# CM5_Adapter.net
KiCad netlist of a schematic drawn in Altium Designer
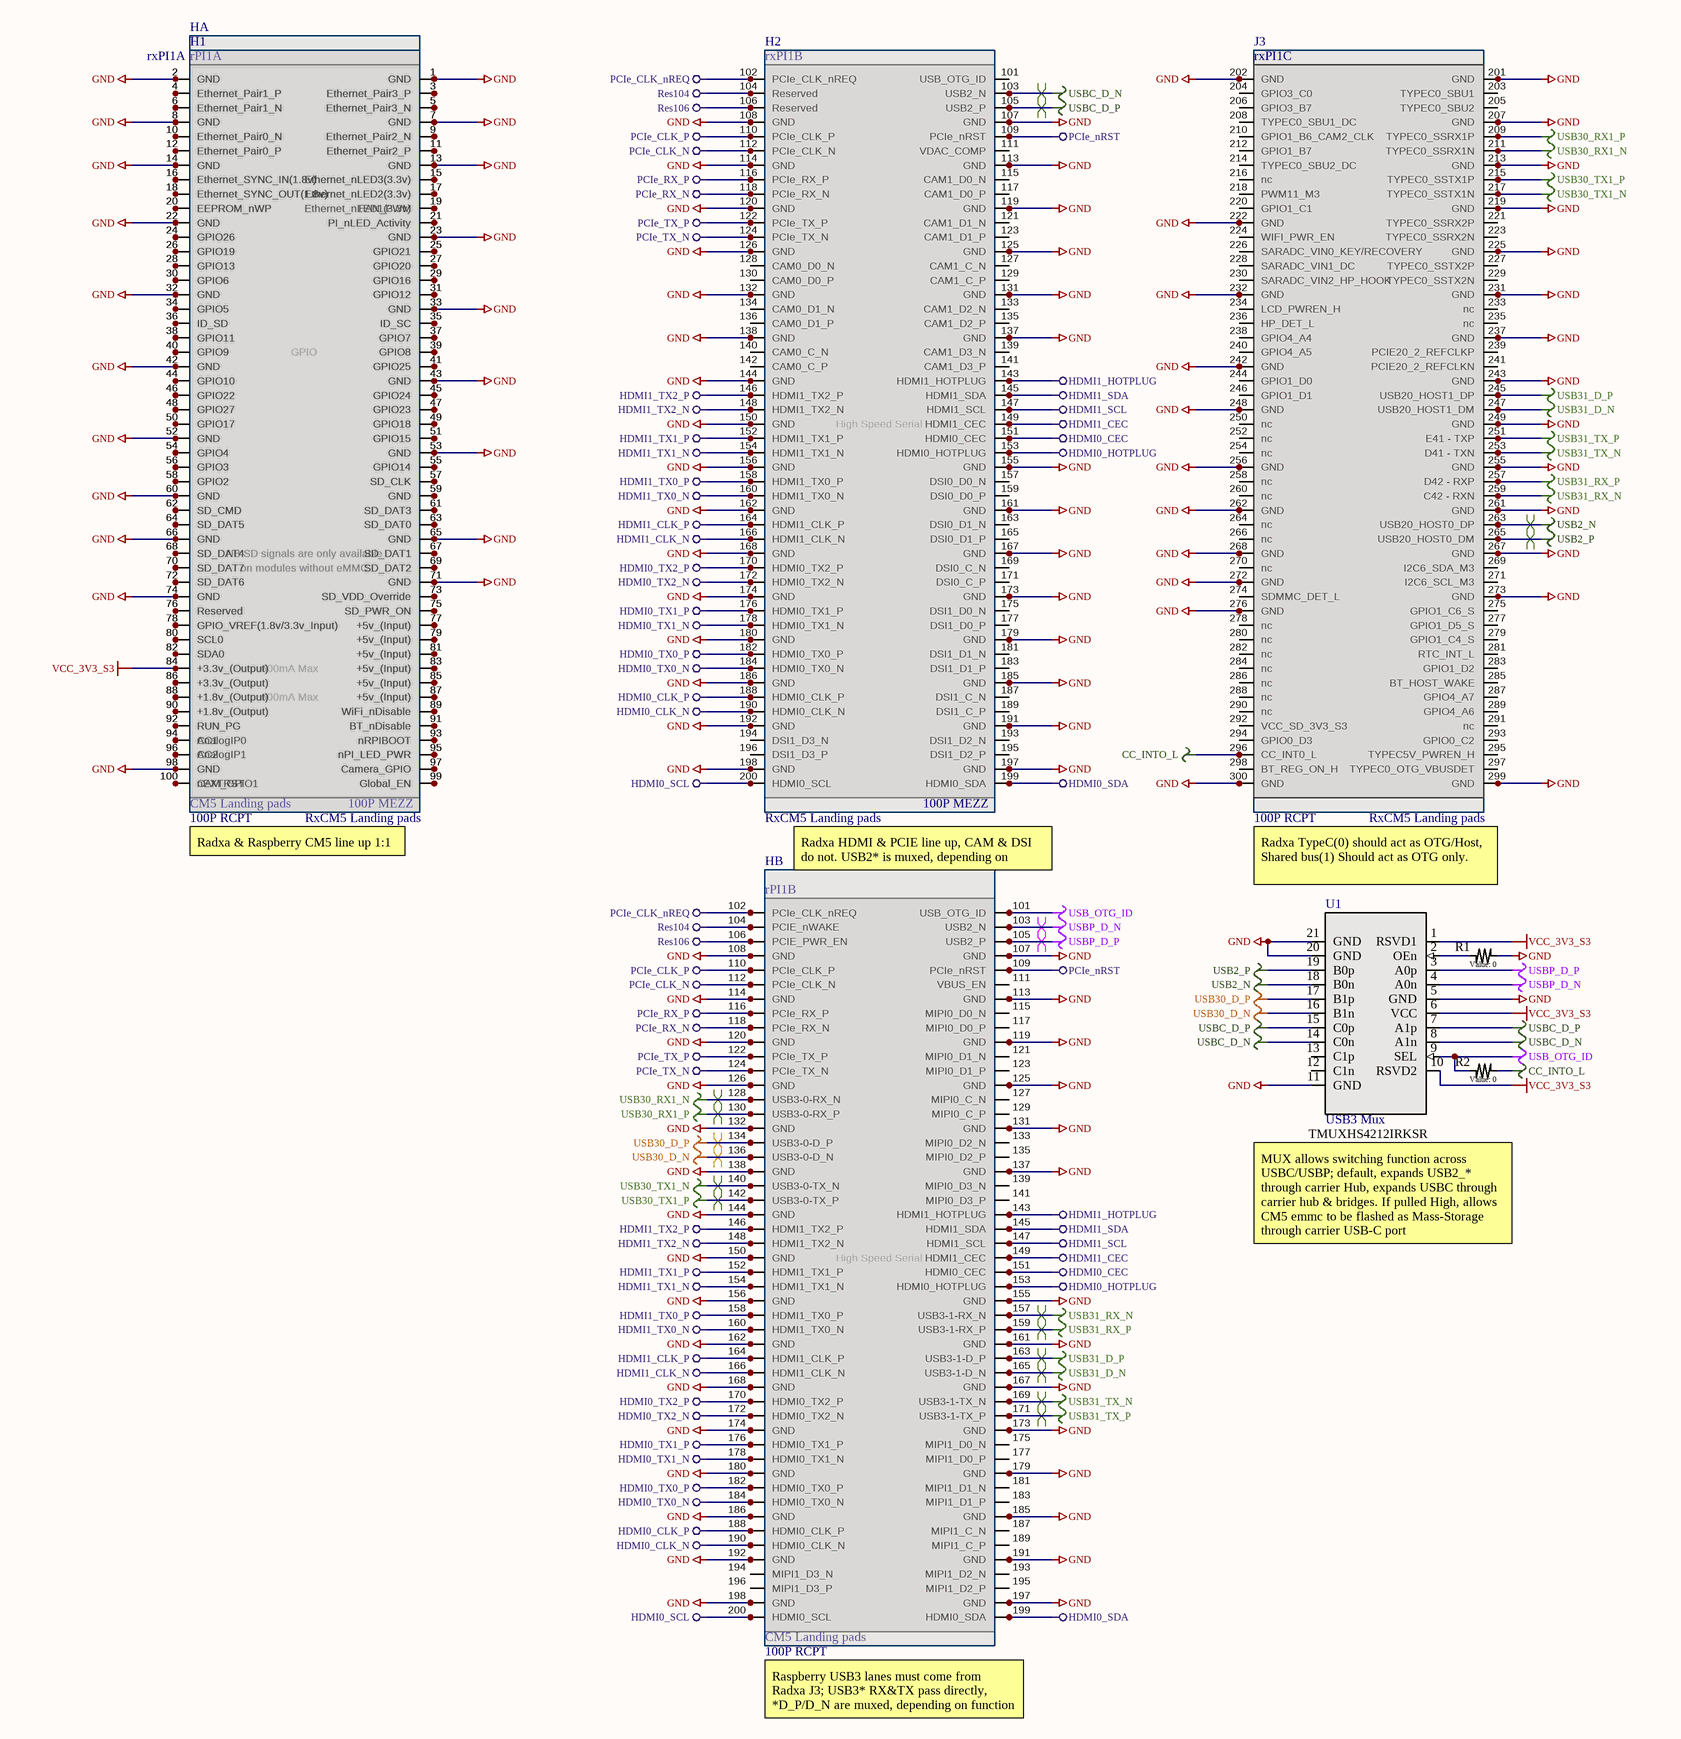
[diagram p0: CM5 Adapter.SchDoc]

(export (version "E")
  (design (tool "Eeschema 10.0.6"))
  (components
    (comp (ref "H1")
      (value "100P RCPT")
      (footprint "DF40C-100DS-0.4V(51)")
      (description "100 Position Connector Receptacle, Center Strip Contacts Surface Mount Gold")
      (fields (field (name "MF") "Hirose") (field (name "MP") "DF40C-100DS-0.4V(51)"))
      (libsource (lib "") (part "DF40-100DS RCPT_1_1"))
    )
    (comp (ref "H2")
      (value "100P MEZZ")
      (footprint "DF40C-100DS-0.4V(51)")
      (description "100 Position Connector Receptacle, Center Strip Contacts Surface Mount Gold")
      (fields (field (name "MF") "Hirose") (field (name "MP") "DF40C-100DS-0.4V(51)"))
      (libsource (lib "") (part "DF40-100DS RCPT_1_1"))
    )
    (comp (ref "HA")
      (value "100P MEZZ")
      (footprint "DF40C-100DP-0.4V(51)")
      (description "100 Position Connector Receptacle, Center Strip Contacts Surface Mount Gold")
      (fields (field (name "MF") "Hirose") (field (name "MP") "DF40C-100DS-0.4V(51)"))
      (libsource (lib "SOC_Carrier") (part "DF40-XX-100DS RCPT"))
    )
    (comp (ref "HB")
      (value "100P RCPT")
      (footprint "DF40C-100DP-0.4V(51)")
      (description "100 Position Connector Receptacle, Center Strip Contacts Surface Mount Gold")
      (fields (field (name "MF") "Hirose") (field (name "MP") "DF40C-100DS-0.4V(51)"))
      (libsource (lib "SOC_Carrier") (part "DF40-XX-100DS RCPT"))
    )
    (comp (ref "J3")
      (value "100P RCPT")
      (footprint "DF40C-100DS-0.4V(51)")
      (description "100 Position Connector Receptacle, Center Strip Contacts Surface Mount Gold")
      (fields (field (name "MF") "Hirose") (field (name "MP") "DF40C-100DS-0.4V(51)"))
      (libsource (lib "Connectors") (part "DF40-100DS RCPT_1"))
    )
    (comp (ref "R1")
      (value "0")
      (footprint "0603")
      (fields
        (field (name "TOLERANCE") "1%")
        (field (name "POWER") "1/10W")
        (field (name "Comment") "Generic Resistor")
      )
      (libsource (lib "Resistors") (part "Generic Resistor"))
    )
    (comp (ref "R2")
      (value "0")
      (footprint "0603")
      (fields
        (field (name "TOLERANCE") "1%")
        (field (name "POWER") "1/10W")
        (field (name "Comment") "Generic Resistor")
      )
      (libsource (lib "Resistors") (part "Generic Resistor"))
    )
    (comp (ref "rPI1")
      (value "CM5 Landing pads")
      (footprint "rP-200P-CM-REP (top)")
      (libsource (lib "SOC_Carrier") (part "RP-CM5-Rep"))
    )
    (comp (ref "rxPI1")
      (value "RxCM5 Landing pads")
      (footprint "RX-300P-CM-FTPD")
      (libsource (lib "SOC_Carrier") (part "RX-CM5"))
    )
    (comp (ref "U1")
      (value "USB3 Mux")
      (footprint "QFN50P450X250X100-21N")
      (description "2-channel 16-Gbps 2:1/1:2 differential mux/demux")
      (fields
        (field (name "MANUFACTURER_PART_NUMBER") "TMUXHS4212IRKSR")
        (field (name "COPYRIGHT") "Copyright (C) 2023 Ultra Librarian. All rights reserved.")
      )
      (libsource (lib "Misc ICs") (part "TMUXHS4212IRKSR"))
    )
  )
  (nets
    (net (code "1") (name "CC_INTO_L") (class "Default")
      (node (ref "J3") (pin "95") (pinfunction "95_95") (pintype "passive"))
      (node (ref "R2") (pin "2") (pinfunction "2_2") (pintype "passive"))
      (node (ref "rxPI1") (pin "296") (pinfunction "CC_INT0_L_296") (pintype "passive"))
    )
    (net (code "2") (name "GND") (class "Default")
      (node (ref "H1") (pin "1") (pinfunction "1_1") (pintype "passive"))
      (node (ref "H1") (pin "13") (pinfunction "13_13") (pintype "passive"))
      (node (ref "H1") (pin "14") (pinfunction "14_14") (pintype "passive"))
      (node (ref "H1") (pin "2") (pinfunction "2_2") (pintype "passive"))
      (node (ref "H1") (pin "22") (pinfunction "22_22") (pintype "passive"))
      (node (ref "H1") (pin "23") (pinfunction "23_23") (pintype "passive"))
      (node (ref "H1") (pin "32") (pinfunction "32_32") (pintype "passive"))
      (node (ref "H1") (pin "33") (pinfunction "33_33") (pintype "passive"))
      (node (ref "H1") (pin "42") (pinfunction "42_42") (pintype "passive"))
      (node (ref "H1") (pin "43") (pinfunction "43_43") (pintype "passive"))
      (node (ref "H1") (pin "52") (pinfunction "52_52") (pintype "passive"))
      (node (ref "H1") (pin "53") (pinfunction "53_53") (pintype "passive"))
      (node (ref "H1") (pin "60") (pinfunction "60_60") (pintype "passive"))
      (node (ref "H1") (pin "65") (pinfunction "65_65") (pintype "passive"))
      (node (ref "H1") (pin "66") (pinfunction "66_66") (pintype "passive"))
      (node (ref "H1") (pin "7") (pinfunction "7_7") (pintype "passive"))
      (node (ref "H1") (pin "71") (pinfunction "71_71") (pintype "passive"))
      (node (ref "H1") (pin "74") (pinfunction "74_74") (pintype "passive"))
      (node (ref "H1") (pin "8") (pinfunction "8_8") (pintype "passive"))
      (node (ref "H1") (pin "98") (pinfunction "98_98") (pintype "passive"))
      (node (ref "H2") (pin "13") (pinfunction "13_13") (pintype "passive"))
      (node (ref "H2") (pin "14") (pinfunction "14_14") (pintype "passive"))
      (node (ref "H2") (pin "19") (pinfunction "19_19") (pintype "passive"))
      (node (ref "H2") (pin "20") (pinfunction "20_20") (pintype "passive"))
      (node (ref "H2") (pin "25") (pinfunction "25_25") (pintype "passive"))
      (node (ref "H2") (pin "26") (pinfunction "26_26") (pintype "passive"))
      (node (ref "H2") (pin "31") (pinfunction "31_31") (pintype "passive"))
      (node (ref "H2") (pin "32") (pinfunction "32_32") (pintype "passive"))
      (node (ref "H2") (pin "37") (pinfunction "37_37") (pintype "passive"))
      (node (ref "H2") (pin "38") (pinfunction "38_38") (pintype "passive"))
      (node (ref "H2") (pin "44") (pinfunction "44_44") (pintype "passive"))
      (node (ref "H2") (pin "50") (pinfunction "50_50") (pintype "passive"))
      (node (ref "H2") (pin "55") (pinfunction "55_55") (pintype "passive"))
      (node (ref "H2") (pin "56") (pinfunction "56_56") (pintype "passive"))
      (node (ref "H2") (pin "61") (pinfunction "61_61") (pintype "passive"))
      (node (ref "H2") (pin "62") (pinfunction "62_62") (pintype "passive"))
      (node (ref "H2") (pin "67") (pinfunction "67_67") (pintype "passive"))
      (node (ref "H2") (pin "68") (pinfunction "68_68") (pintype "passive"))
      (node (ref "H2") (pin "7") (pinfunction "7_7") (pintype "passive"))
      (node (ref "H2") (pin "73") (pinfunction "73_73") (pintype "passive"))
      (node (ref "H2") (pin "74") (pinfunction "74_74") (pintype "passive"))
      (node (ref "H2") (pin "79") (pinfunction "79_79") (pintype "passive"))
      (node (ref "H2") (pin "8") (pinfunction "8_8") (pintype "passive"))
      (node (ref "H2") (pin "80") (pinfunction "80_80") (pintype "passive"))
      (node (ref "H2") (pin "85") (pinfunction "85_85") (pintype "passive"))
      (node (ref "H2") (pin "86") (pinfunction "86_86") (pintype "passive"))
      (node (ref "H2") (pin "91") (pinfunction "91_91") (pintype "passive"))
      (node (ref "H2") (pin "92") (pinfunction "92_92") (pintype "passive"))
      (node (ref "H2") (pin "97") (pinfunction "97_97") (pintype "passive"))
      (node (ref "H2") (pin "98") (pinfunction "98_98") (pintype "passive"))
      (node (ref "HA") (pin "1") (pinfunction "1_1") (pintype "passive"))
      (node (ref "HA") (pin "13") (pinfunction "13_13") (pintype "passive"))
      (node (ref "HA") (pin "14") (pinfunction "14_14") (pintype "passive"))
      (node (ref "HA") (pin "2") (pinfunction "2_2") (pintype "passive"))
      (node (ref "HA") (pin "21") (pinfunction "21_21") (pintype "passive"))
      (node (ref "HA") (pin "24") (pinfunction "24_24") (pintype "passive"))
      (node (ref "HA") (pin "31") (pinfunction "31_31") (pintype "passive"))
      (node (ref "HA") (pin "34") (pinfunction "34_34") (pintype "passive"))
      (node (ref "HA") (pin "41") (pinfunction "41_41") (pintype "passive"))
      (node (ref "HA") (pin "44") (pinfunction "44_44") (pintype "passive"))
      (node (ref "HA") (pin "51") (pinfunction "51_51") (pintype "passive"))
      (node (ref "HA") (pin "54") (pinfunction "54_54") (pintype "passive"))
      (node (ref "HA") (pin "59") (pinfunction "59_59") (pintype "passive"))
      (node (ref "HA") (pin "65") (pinfunction "65_65") (pintype "passive"))
      (node (ref "HA") (pin "66") (pinfunction "66_66") (pintype "passive"))
      (node (ref "HA") (pin "7") (pinfunction "7_7") (pintype "passive"))
      (node (ref "HA") (pin "72") (pinfunction "72_72") (pintype "passive"))
      (node (ref "HA") (pin "73") (pinfunction "73_73") (pintype "passive"))
      (node (ref "HA") (pin "8") (pinfunction "8_8") (pintype "passive"))
      (node (ref "HA") (pin "97") (pinfunction "97_97") (pintype "passive"))
      (node (ref "HB") (pin "13") (pinfunction "13_13") (pintype "passive"))
      (node (ref "HB") (pin "14") (pinfunction "14_14") (pintype "passive"))
      (node (ref "HB") (pin "19") (pinfunction "19_19") (pintype "passive"))
      (node (ref "HB") (pin "20") (pinfunction "20_20") (pintype "passive"))
      (node (ref "HB") (pin "25") (pinfunction "25_25") (pintype "passive"))
      (node (ref "HB") (pin "26") (pinfunction "26_26") (pintype "passive"))
      (node (ref "HB") (pin "31") (pinfunction "31_31") (pintype "passive"))
      (node (ref "HB") (pin "32") (pinfunction "32_32") (pintype "passive"))
      (node (ref "HB") (pin "37") (pinfunction "37_37") (pintype "passive"))
      (node (ref "HB") (pin "38") (pinfunction "38_38") (pintype "passive"))
      (node (ref "HB") (pin "43") (pinfunction "43_43") (pintype "passive"))
      (node (ref "HB") (pin "49") (pinfunction "49_49") (pintype "passive"))
      (node (ref "HB") (pin "55") (pinfunction "55_55") (pintype "passive"))
      (node (ref "HB") (pin "56") (pinfunction "56_56") (pintype "passive"))
      (node (ref "HB") (pin "61") (pinfunction "61_61") (pintype "passive"))
      (node (ref "HB") (pin "62") (pinfunction "62_62") (pintype "passive"))
      (node (ref "HB") (pin "67") (pinfunction "67_67") (pintype "passive"))
      (node (ref "HB") (pin "68") (pinfunction "68_68") (pintype "passive"))
      (node (ref "HB") (pin "7") (pinfunction "7_7") (pintype "passive"))
      (node (ref "HB") (pin "73") (pinfunction "73_73") (pintype "passive"))
      (node (ref "HB") (pin "74") (pinfunction "74_74") (pintype "passive"))
      (node (ref "HB") (pin "79") (pinfunction "79_79") (pintype "passive"))
      (node (ref "HB") (pin "8") (pinfunction "8_8") (pintype "passive"))
      (node (ref "HB") (pin "80") (pinfunction "80_80") (pintype "passive"))
      (node (ref "HB") (pin "85") (pinfunction "85_85") (pintype "passive"))
      (node (ref "HB") (pin "86") (pinfunction "86_86") (pintype "passive"))
      (node (ref "HB") (pin "91") (pinfunction "91_91") (pintype "passive"))
      (node (ref "HB") (pin "92") (pinfunction "92_92") (pintype "passive"))
      (node (ref "HB") (pin "97") (pinfunction "97_97") (pintype "passive"))
      (node (ref "HB") (pin "98") (pinfunction "98_98") (pintype "passive"))
      (node (ref "J3") (pin "1") (pinfunction "1_1") (pintype "passive"))
      (node (ref "J3") (pin "100") (pinfunction "100_100") (pintype "passive"))
      (node (ref "J3") (pin "14") (pinfunction "14_14") (pintype "passive"))
      (node (ref "J3") (pin "2") (pinfunction "2_2") (pintype "passive"))
      (node (ref "J3") (pin "20") (pinfunction "20_20") (pintype "passive"))
      (node (ref "J3") (pin "21") (pinfunction "21_21") (pintype "passive"))
      (node (ref "J3") (pin "26") (pinfunction "26_26") (pintype "passive"))
      (node (ref "J3") (pin "31") (pinfunction "31_31") (pintype "passive"))
      (node (ref "J3") (pin "32") (pinfunction "32_32") (pintype "passive"))
      (node (ref "J3") (pin "38") (pinfunction "38_38") (pintype "passive"))
      (node (ref "J3") (pin "41") (pinfunction "41_41") (pintype "passive"))
      (node (ref "J3") (pin "44") (pinfunction "44_44") (pintype "passive"))
      (node (ref "J3") (pin "47") (pinfunction "47_47") (pintype "passive"))
      (node (ref "J3") (pin "50") (pinfunction "50_50") (pintype "passive"))
      (node (ref "J3") (pin "55") (pinfunction "55_55") (pintype "passive"))
      (node (ref "J3") (pin "56") (pinfunction "56_56") (pintype "passive"))
      (node (ref "J3") (pin "61") (pinfunction "61_61") (pintype "passive"))
      (node (ref "J3") (pin "62") (pinfunction "62_62") (pintype "passive"))
      (node (ref "J3") (pin "67") (pinfunction "67_67") (pintype "passive"))
      (node (ref "J3") (pin "68") (pinfunction "68_68") (pintype "passive"))
      (node (ref "J3") (pin "71") (pinfunction "71_71") (pintype "passive"))
      (node (ref "J3") (pin "74") (pinfunction "74_74") (pintype "passive"))
      (node (ref "J3") (pin "75") (pinfunction "75_75") (pintype "passive"))
      (node (ref "J3") (pin "8") (pinfunction "8_8") (pintype "passive"))
      (node (ref "J3") (pin "99") (pinfunction "99_99") (pintype "passive"))
      (node (ref "R1") (pin "2") (pinfunction "2_2") (pintype "passive"))
      (node (ref "U1") (pin "11") (pinfunction "GND_11") (pintype "power_in"))
      (node (ref "U1") (pin "20") (pinfunction "GND_20") (pintype "power_in"))
      (node (ref "U1") (pin "21") (pinfunction "GND_21") (pintype "power_in"))
      (node (ref "U1") (pin "5") (pinfunction "GND_5") (pintype "power_in"))
      (node (ref "rPI1") (pin "1") (pinfunction "GND_1") (pintype "passive"))
      (node (ref "rPI1") (pin "107") (pinfunction "GND_107") (pintype "passive"))
      (node (ref "rPI1") (pin "108") (pinfunction "GND_108") (pintype "passive"))
      (node (ref "rPI1") (pin "113") (pinfunction "GND_113") (pintype "passive"))
      (node (ref "rPI1") (pin "114") (pinfunction "GND_114") (pintype "passive"))
      (node (ref "rPI1") (pin "119") (pinfunction "GND_119") (pintype "passive"))
      (node (ref "rPI1") (pin "120") (pinfunction "GND_120") (pintype "passive"))
      (node (ref "rPI1") (pin "125") (pinfunction "GND_125") (pintype "passive"))
      (node (ref "rPI1") (pin "126") (pinfunction "GND_126") (pintype "passive"))
      (node (ref "rPI1") (pin "13") (pinfunction "GND_13") (pintype "passive"))
      (node (ref "rPI1") (pin "131") (pinfunction "GND_131") (pintype "passive"))
      (node (ref "rPI1") (pin "132") (pinfunction "GND_132") (pintype "passive"))
      (node (ref "rPI1") (pin "137") (pinfunction "GND_137") (pintype "passive"))
      (node (ref "rPI1") (pin "138") (pinfunction "GND_138") (pintype "passive"))
      (node (ref "rPI1") (pin "14") (pinfunction "GND_14") (pintype "passive"))
      (node (ref "rPI1") (pin "144") (pinfunction "GND_144") (pintype "passive"))
      (node (ref "rPI1") (pin "150") (pinfunction "GND_150") (pintype "passive"))
      (node (ref "rPI1") (pin "155") (pinfunction "GND_155") (pintype "passive"))
      (node (ref "rPI1") (pin "156") (pinfunction "GND_156") (pintype "passive"))
      (node (ref "rPI1") (pin "161") (pinfunction "GND_161") (pintype "passive"))
      (node (ref "rPI1") (pin "162") (pinfunction "GND_162") (pintype "passive"))
      (node (ref "rPI1") (pin "167") (pinfunction "GND_167") (pintype "passive"))
      (node (ref "rPI1") (pin "168") (pinfunction "GND_168") (pintype "passive"))
      (node (ref "rPI1") (pin "173") (pinfunction "GND_173") (pintype "passive"))
      (node (ref "rPI1") (pin "174") (pinfunction "GND_174") (pintype "passive"))
      (node (ref "rPI1") (pin "179") (pinfunction "GND_179") (pintype "passive"))
      (node (ref "rPI1") (pin "180") (pinfunction "GND_180") (pintype "passive"))
      (node (ref "rPI1") (pin "185") (pinfunction "GND_185") (pintype "passive"))
      (node (ref "rPI1") (pin "186") (pinfunction "GND_186") (pintype "passive"))
      (node (ref "rPI1") (pin "191") (pinfunction "GND_191") (pintype "passive"))
      (node (ref "rPI1") (pin "192") (pinfunction "GND_192") (pintype "passive"))
      (node (ref "rPI1") (pin "197") (pinfunction "GND_197") (pintype "passive"))
      (node (ref "rPI1") (pin "198") (pinfunction "GND_198") (pintype "passive"))
      (node (ref "rPI1") (pin "2") (pinfunction "GND_2") (pintype "passive"))
      (node (ref "rPI1") (pin "22") (pinfunction "GND_22") (pintype "passive"))
      (node (ref "rPI1") (pin "23") (pinfunction "GND_23") (pintype "passive"))
      (node (ref "rPI1") (pin "32") (pinfunction "GND_32") (pintype "passive"))
      (node (ref "rPI1") (pin "33") (pinfunction "GND_33") (pintype "passive"))
      (node (ref "rPI1") (pin "42") (pinfunction "GND_42") (pintype "passive"))
      (node (ref "rPI1") (pin "43") (pinfunction "GND_43") (pintype "passive"))
      (node (ref "rPI1") (pin "52") (pinfunction "GND_52") (pintype "passive"))
      (node (ref "rPI1") (pin "53") (pinfunction "GND_53") (pintype "passive"))
      (node (ref "rPI1") (pin "60") (pinfunction "GND_60") (pintype "passive"))
      (node (ref "rPI1") (pin "65") (pinfunction "GND_65") (pintype "passive"))
      (node (ref "rPI1") (pin "66") (pinfunction "GND_66") (pintype "passive"))
      (node (ref "rPI1") (pin "7") (pinfunction "GND_7") (pintype "passive"))
      (node (ref "rPI1") (pin "71") (pinfunction "GND_71") (pintype "passive"))
      (node (ref "rPI1") (pin "74") (pinfunction "GND_74") (pintype "passive"))
      (node (ref "rPI1") (pin "8") (pinfunction "GND_8") (pintype "passive"))
      (node (ref "rPI1") (pin "98") (pinfunction "GND_98") (pintype "passive"))
      (node (ref "rxPI1") (pin "1") (pinfunction "GND_1") (pintype "passive"))
      (node (ref "rxPI1") (pin "107") (pinfunction "GND_107") (pintype "passive"))
      (node (ref "rxPI1") (pin "108") (pinfunction "GND_108") (pintype "passive"))
      (node (ref "rxPI1") (pin "113") (pinfunction "GND_113") (pintype "passive"))
      (node (ref "rxPI1") (pin "114") (pinfunction "GND_114") (pintype "passive"))
      (node (ref "rxPI1") (pin "119") (pinfunction "GND_119") (pintype "passive"))
      (node (ref "rxPI1") (pin "120") (pinfunction "GND_120") (pintype "passive"))
      (node (ref "rxPI1") (pin "125") (pinfunction "GND_125") (pintype "passive"))
      (node (ref "rxPI1") (pin "126") (pinfunction "GND_126") (pintype "passive"))
      (node (ref "rxPI1") (pin "13") (pinfunction "GND_13") (pintype "passive"))
      (node (ref "rxPI1") (pin "131") (pinfunction "GND_131") (pintype "passive"))
      (node (ref "rxPI1") (pin "132") (pinfunction "GND_132") (pintype "passive"))
      (node (ref "rxPI1") (pin "137") (pinfunction "GND_137") (pintype "passive"))
      (node (ref "rxPI1") (pin "138") (pinfunction "GND_138") (pintype "passive"))
      (node (ref "rxPI1") (pin "14") (pinfunction "GND_14") (pintype "passive"))
      (node (ref "rxPI1") (pin "144") (pinfunction "GND_144") (pintype "passive"))
      (node (ref "rxPI1") (pin "150") (pinfunction "GND_150") (pintype "passive"))
      (node (ref "rxPI1") (pin "155") (pinfunction "GND_155") (pintype "passive"))
      (node (ref "rxPI1") (pin "156") (pinfunction "GND_156") (pintype "passive"))
      (node (ref "rxPI1") (pin "161") (pinfunction "GND_161") (pintype "passive"))
      (node (ref "rxPI1") (pin "162") (pinfunction "GND_162") (pintype "passive"))
      (node (ref "rxPI1") (pin "167") (pinfunction "GND_167") (pintype "passive"))
      (node (ref "rxPI1") (pin "168") (pinfunction "GND_168") (pintype "passive"))
      (node (ref "rxPI1") (pin "173") (pinfunction "GND_173") (pintype "passive"))
      (node (ref "rxPI1") (pin "174") (pinfunction "GND_174") (pintype "passive"))
      (node (ref "rxPI1") (pin "179") (pinfunction "GND_179") (pintype "passive"))
      (node (ref "rxPI1") (pin "180") (pinfunction "GND_180") (pintype "passive"))
      (node (ref "rxPI1") (pin "185") (pinfunction "GND_185") (pintype "passive"))
      (node (ref "rxPI1") (pin "186") (pinfunction "GND_186") (pintype "passive"))
      (node (ref "rxPI1") (pin "191") (pinfunction "GND_191") (pintype "passive"))
      (node (ref "rxPI1") (pin "192") (pinfunction "GND_192") (pintype "passive"))
      (node (ref "rxPI1") (pin "197") (pinfunction "GND_197") (pintype "passive"))
      (node (ref "rxPI1") (pin "198") (pinfunction "GND_198") (pintype "passive"))
      (node (ref "rxPI1") (pin "2") (pinfunction "GND_2") (pintype "passive"))
      (node (ref "rxPI1") (pin "201") (pinfunction "GND_201") (pintype "passive"))
      (node (ref "rxPI1") (pin "202") (pinfunction "GND_202") (pintype "passive"))
      (node (ref "rxPI1") (pin "207") (pinfunction "GND_207") (pintype "passive"))
      (node (ref "rxPI1") (pin "213") (pinfunction "GND_213") (pintype "passive"))
      (node (ref "rxPI1") (pin "219") (pinfunction "GND_219") (pintype "passive"))
      (node (ref "rxPI1") (pin "22") (pinfunction "GND_22") (pintype "passive"))
      (node (ref "rxPI1") (pin "222") (pinfunction "GND_222") (pintype "passive"))
      (node (ref "rxPI1") (pin "225") (pinfunction "GND_225") (pintype "passive"))
      (node (ref "rxPI1") (pin "23") (pinfunction "GND_23") (pintype "passive"))
      (node (ref "rxPI1") (pin "231") (pinfunction "GND_231") (pintype "passive"))
      (node (ref "rxPI1") (pin "232") (pinfunction "GND_232") (pintype "passive"))
      (node (ref "rxPI1") (pin "237") (pinfunction "GND_237") (pintype "passive"))
      (node (ref "rxPI1") (pin "242") (pinfunction "GND_242") (pintype "passive"))
      (node (ref "rxPI1") (pin "243") (pinfunction "GND_243") (pintype "passive"))
      (node (ref "rxPI1") (pin "248") (pinfunction "GND_248") (pintype "passive"))
      (node (ref "rxPI1") (pin "249") (pinfunction "GND_249") (pintype "passive"))
      (node (ref "rxPI1") (pin "255") (pinfunction "GND_255") (pintype "passive"))
      (node (ref "rxPI1") (pin "256") (pinfunction "GND_256") (pintype "passive"))
      (node (ref "rxPI1") (pin "261") (pinfunction "GND_261") (pintype "passive"))
      (node (ref "rxPI1") (pin "262") (pinfunction "GND_262") (pintype "passive"))
      (node (ref "rxPI1") (pin "267") (pinfunction "GND_267") (pintype "passive"))
      (node (ref "rxPI1") (pin "268") (pinfunction "GND_268") (pintype "passive"))
      (node (ref "rxPI1") (pin "272") (pinfunction "GND_272") (pintype "passive"))
      (node (ref "rxPI1") (pin "273") (pinfunction "GND_273") (pintype "passive"))
      (node (ref "rxPI1") (pin "276") (pinfunction "GND_276") (pintype "passive"))
      (node (ref "rxPI1") (pin "299") (pinfunction "GND_299") (pintype "passive"))
      (node (ref "rxPI1") (pin "300") (pinfunction "GND_300") (pintype "passive"))
      (node (ref "rxPI1") (pin "32") (pinfunction "GND_32") (pintype "passive"))
      (node (ref "rxPI1") (pin "33") (pinfunction "GND_33") (pintype "passive"))
      (node (ref "rxPI1") (pin "42") (pinfunction "GND_42") (pintype "passive"))
      (node (ref "rxPI1") (pin "43") (pinfunction "GND_43") (pintype "passive"))
      (node (ref "rxPI1") (pin "52") (pinfunction "GND_52") (pintype "passive"))
      (node (ref "rxPI1") (pin "53") (pinfunction "GND_53") (pintype "passive"))
      (node (ref "rxPI1") (pin "60") (pinfunction "GND_60") (pintype "passive"))
      (node (ref "rxPI1") (pin "65") (pinfunction "GND_65") (pintype "passive"))
      (node (ref "rxPI1") (pin "66") (pinfunction "GND_66") (pintype "passive"))
      (node (ref "rxPI1") (pin "7") (pinfunction "GND_7") (pintype "passive"))
      (node (ref "rxPI1") (pin "71") (pinfunction "GND_71") (pintype "passive"))
      (node (ref "rxPI1") (pin "74") (pinfunction "GND_74") (pintype "passive"))
      (node (ref "rxPI1") (pin "8") (pinfunction "GND_8") (pintype "passive"))
      (node (ref "rxPI1") (pin "98") (pinfunction "GND_98") (pintype "passive"))
    )
    (net (code "3") (name "HDMI0_CEC") (class "Default")
      (node (ref "H2") (pin "51") (pinfunction "51_51") (pintype "passive"))
      (node (ref "HB") (pin "52") (pinfunction "52_52") (pintype "passive"))
      (node (ref "rPI1") (pin "151") (pinfunction "HDMI0_CEC_151") (pintype "passive"))
      (node (ref "rxPI1") (pin "151") (pinfunction "HDMI0_CEC_151") (pintype "passive"))
    )
    (net (code "4") (name "HDMI0_CLK_N") (class "Default")
      (node (ref "H2") (pin "90") (pinfunction "90_90") (pintype "passive"))
      (node (ref "HB") (pin "89") (pinfunction "89_89") (pintype "passive"))
      (node (ref "rPI1") (pin "190") (pinfunction "HDMI0_CLK_N_190") (pintype "passive"))
      (node (ref "rxPI1") (pin "190") (pinfunction "HDMI0_CLK_N_190") (pintype "passive"))
    )
    (net (code "5") (name "HDMI0_CLK_P") (class "Default")
      (node (ref "H2") (pin "88") (pinfunction "88_88") (pintype "passive"))
      (node (ref "HB") (pin "87") (pinfunction "87_87") (pintype "passive"))
      (node (ref "rPI1") (pin "188") (pinfunction "HDMI0_CLK_P_188") (pintype "passive"))
      (node (ref "rxPI1") (pin "188") (pinfunction "HDMI0_CLK_P_188") (pintype "passive"))
    )
    (net (code "6") (name "HDMI0_HOTPLUG") (class "Default")
      (node (ref "H2") (pin "53") (pinfunction "53_53") (pintype "passive"))
      (node (ref "HB") (pin "54") (pinfunction "54_54") (pintype "passive"))
      (node (ref "rPI1") (pin "153") (pinfunction "HDMI0_HOTPLUG_153") (pintype "passive"))
      (node (ref "rxPI1") (pin "153") (pinfunction "HDMI0_HOTPLUG_153") (pintype "passive"))
    )
    (net (code "7") (name "HDMI0_SCL") (class "Default")
      (node (ref "H2") (pin "100") (pinfunction "100_100") (pintype "passive"))
      (node (ref "HB") (pin "99") (pinfunction "99_99") (pintype "passive"))
      (node (ref "rPI1") (pin "200") (pinfunction "HDMI0_SCL_200") (pintype "passive"))
      (node (ref "rxPI1") (pin "200") (pinfunction "HDMI0_SCL_200") (pintype "passive"))
    )
    (net (code "8") (name "HDMI0_SDA") (class "Default")
      (node (ref "H2") (pin "99") (pinfunction "99_99") (pintype "passive"))
      (node (ref "HB") (pin "100") (pinfunction "100_100") (pintype "passive"))
      (node (ref "rPI1") (pin "199") (pinfunction "HDMI0_SDA_199") (pintype "passive"))
      (node (ref "rxPI1") (pin "199") (pinfunction "HDMI0_SDA_199") (pintype "passive"))
    )
    (net (code "9") (name "HDMI0_TX0_N") (class "Default")
      (node (ref "H2") (pin "84") (pinfunction "84_84") (pintype "passive"))
      (node (ref "HB") (pin "83") (pinfunction "83_83") (pintype "passive"))
      (node (ref "rPI1") (pin "184") (pinfunction "HDMI0_TX0_N_184") (pintype "passive"))
      (node (ref "rxPI1") (pin "184") (pinfunction "HDMI0_TX0_N_184") (pintype "passive"))
    )
    (net (code "10") (name "HDMI0_TX0_P") (class "Default")
      (node (ref "H2") (pin "82") (pinfunction "82_82") (pintype "passive"))
      (node (ref "HB") (pin "81") (pinfunction "81_81") (pintype "passive"))
      (node (ref "rPI1") (pin "182") (pinfunction "HDMI0_TX0_P_182") (pintype "passive"))
      (node (ref "rxPI1") (pin "182") (pinfunction "HDMI0_TX0_P_182") (pintype "passive"))
    )
    (net (code "11") (name "HDMI0_TX1_N") (class "Default")
      (node (ref "H2") (pin "78") (pinfunction "78_78") (pintype "passive"))
      (node (ref "HB") (pin "77") (pinfunction "77_77") (pintype "passive"))
      (node (ref "rPI1") (pin "178") (pinfunction "HDMI0_TX1_N_178") (pintype "passive"))
      (node (ref "rxPI1") (pin "178") (pinfunction "HDMI0_TX1_N_178") (pintype "passive"))
    )
    (net (code "12") (name "HDMI0_TX1_P") (class "Default")
      (node (ref "H2") (pin "76") (pinfunction "76_76") (pintype "passive"))
      (node (ref "HB") (pin "75") (pinfunction "75_75") (pintype "passive"))
      (node (ref "rPI1") (pin "176") (pinfunction "HDMI0_TX1_P_176") (pintype "passive"))
      (node (ref "rxPI1") (pin "176") (pinfunction "HDMI0_TX1_P_176") (pintype "passive"))
    )
    (net (code "13") (name "HDMI0_TX2_N") (class "Default")
      (node (ref "H2") (pin "72") (pinfunction "72_72") (pintype "passive"))
      (node (ref "HB") (pin "71") (pinfunction "71_71") (pintype "passive"))
      (node (ref "rPI1") (pin "172") (pinfunction "HDMI0_TX2_N_172") (pintype "passive"))
      (node (ref "rxPI1") (pin "172") (pinfunction "HDMI0_TX2_N_172") (pintype "passive"))
    )
    (net (code "14") (name "HDMI0_TX2_P") (class "Default")
      (node (ref "H2") (pin "70") (pinfunction "70_70") (pintype "passive"))
      (node (ref "HB") (pin "69") (pinfunction "69_69") (pintype "passive"))
      (node (ref "rPI1") (pin "170") (pinfunction "HDMI0_TX2_P_170") (pintype "passive"))
      (node (ref "rxPI1") (pin "170") (pinfunction "HDMI0_TX2_P_170") (pintype "passive"))
    )
    (net (code "15") (name "HDMI1_CEC") (class "Default")
      (node (ref "H2") (pin "49") (pinfunction "49_49") (pintype "passive"))
      (node (ref "HB") (pin "50") (pinfunction "50_50") (pintype "passive"))
      (node (ref "rPI1") (pin "149") (pinfunction "HDMI1_CEC_149") (pintype "passive"))
      (node (ref "rxPI1") (pin "149") (pinfunction "HDMI1_CEC_149") (pintype "passive"))
    )
    (net (code "16") (name "HDMI1_CLK_N") (class "Default")
      (node (ref "H2") (pin "66") (pinfunction "66_66") (pintype "passive"))
      (node (ref "HB") (pin "65") (pinfunction "65_65") (pintype "passive"))
      (node (ref "rPI1") (pin "166") (pinfunction "HDMI1_CLK_N_166") (pintype "passive"))
      (node (ref "rxPI1") (pin "166") (pinfunction "HDMI1_CLK_N_166") (pintype "passive"))
    )
    (net (code "17") (name "HDMI1_CLK_P") (class "Default")
      (node (ref "H2") (pin "64") (pinfunction "64_64") (pintype "passive"))
      (node (ref "HB") (pin "63") (pinfunction "63_63") (pintype "passive"))
      (node (ref "rPI1") (pin "164") (pinfunction "HDMI1_CLK_P_164") (pintype "passive"))
      (node (ref "rxPI1") (pin "164") (pinfunction "HDMI1_CLK_P_164") (pintype "passive"))
    )
    (net (code "18") (name "HDMI1_HOTPLUG") (class "Default")
      (node (ref "H2") (pin "43") (pinfunction "43_43") (pintype "passive"))
      (node (ref "HB") (pin "44") (pinfunction "44_44") (pintype "passive"))
      (node (ref "rPI1") (pin "143") (pinfunction "HDMI1_HOTPLUG_143") (pintype "passive"))
      (node (ref "rxPI1") (pin "143") (pinfunction "HDMI1_HOTPLUG_143") (pintype "passive"))
    )
    (net (code "19") (name "HDMI1_SCL") (class "Default")
      (node (ref "H2") (pin "47") (pinfunction "47_47") (pintype "passive"))
      (node (ref "HB") (pin "48") (pinfunction "48_48") (pintype "passive"))
      (node (ref "rPI1") (pin "147") (pinfunction "HDMI1_SCL_147") (pintype "passive"))
      (node (ref "rxPI1") (pin "147") (pinfunction "HDMI1_SCL_147") (pintype "passive"))
    )
    (net (code "20") (name "HDMI1_SDA") (class "Default")
      (node (ref "H2") (pin "45") (pinfunction "45_45") (pintype "passive"))
      (node (ref "HB") (pin "46") (pinfunction "46_46") (pintype "passive"))
      (node (ref "rPI1") (pin "145") (pinfunction "HDMI1_SDA_145") (pintype "passive"))
      (node (ref "rxPI1") (pin "145") (pinfunction "HDMI1_SDA_145") (pintype "passive"))
    )
    (net (code "21") (name "HDMI1_TX0_N") (class "Default")
      (node (ref "H2") (pin "60") (pinfunction "60_60") (pintype "passive"))
      (node (ref "HB") (pin "59") (pinfunction "59_59") (pintype "passive"))
      (node (ref "rPI1") (pin "160") (pinfunction "HDMI1_TX0_N_160") (pintype "passive"))
      (node (ref "rxPI1") (pin "160") (pinfunction "HDMI1_TX0_N_160") (pintype "passive"))
    )
    (net (code "22") (name "HDMI1_TX0_P") (class "Default")
      (node (ref "H2") (pin "58") (pinfunction "58_58") (pintype "passive"))
      (node (ref "HB") (pin "57") (pinfunction "57_57") (pintype "passive"))
      (node (ref "rPI1") (pin "158") (pinfunction "HDMI1_TX0_P_158") (pintype "passive"))
      (node (ref "rxPI1") (pin "158") (pinfunction "HDMI1_TX0_P_158") (pintype "passive"))
    )
    (net (code "23") (name "HDMI1_TX1_N") (class "Default")
      (node (ref "H2") (pin "54") (pinfunction "54_54") (pintype "passive"))
      (node (ref "HB") (pin "53") (pinfunction "53_53") (pintype "passive"))
      (node (ref "rPI1") (pin "154") (pinfunction "HDMI1_TX1_N_154") (pintype "passive"))
      (node (ref "rxPI1") (pin "154") (pinfunction "HDMI1_TX1_N_154") (pintype "passive"))
    )
    (net (code "24") (name "HDMI1_TX1_P") (class "Default")
      (node (ref "H2") (pin "52") (pinfunction "52_52") (pintype "passive"))
      (node (ref "HB") (pin "51") (pinfunction "51_51") (pintype "passive"))
      (node (ref "rPI1") (pin "152") (pinfunction "HDMI1_TX1_P_152") (pintype "passive"))
      (node (ref "rxPI1") (pin "152") (pinfunction "HDMI1_TX1_P_152") (pintype "passive"))
    )
    (net (code "25") (name "HDMI1_TX2_N") (class "Default")
      (node (ref "H2") (pin "48") (pinfunction "48_48") (pintype "passive"))
      (node (ref "HB") (pin "47") (pinfunction "47_47") (pintype "passive"))
      (node (ref "rPI1") (pin "148") (pinfunction "HDMI1_TX2_N_148") (pintype "passive"))
      (node (ref "rxPI1") (pin "148") (pinfunction "HDMI1_TX2_N_148") (pintype "passive"))
    )
    (net (code "26") (name "HDMI1_TX2_P") (class "Default")
      (node (ref "H2") (pin "46") (pinfunction "46_46") (pintype "passive"))
      (node (ref "HB") (pin "45") (pinfunction "45_45") (pintype "passive"))
      (node (ref "rPI1") (pin "146") (pinfunction "HDMI1_TX2_P_146") (pintype "passive"))
      (node (ref "rxPI1") (pin "146") (pinfunction "HDMI1_TX2_P_146") (pintype "passive"))
    )
    (net (code "27") (name "Net-(H1-Pad59)") (class "Default")
      (node (ref "H1") (pin "59") (pinfunction "59_59") (pintype "passive"))
      (node (ref "HA") (pin "60") (pinfunction "60_60") (pintype "passive"))
      (node (ref "rPI1") (pin "59") (pinfunction "GND_59") (pintype "passive"))
      (node (ref "rxPI1") (pin "59") (pinfunction "GND_59") (pintype "passive"))
    )
    (net (code "28") (name "Net-(H1-Pad77)") (class "Default")
      (node (ref "H1") (pin "77") (pinfunction "77_77") (pintype "passive"))
      (node (ref "HA") (pin "78") (pinfunction "78_78") (pintype "passive"))
      (node (ref "rPI1") (pin "77") (pinfunction "+5v_(Input)_77") (pintype "passive"))
      (node (ref "rxPI1") (pin "77") (pinfunction "+5v_(Input)_77") (pintype "passive"))
    )
    (net (code "29") (name "Net-(H1-Pad79)") (class "Default")
      (node (ref "H1") (pin "79") (pinfunction "79_79") (pintype "passive"))
      (node (ref "HA") (pin "80") (pinfunction "80_80") (pintype "passive"))
      (node (ref "rPI1") (pin "79") (pinfunction "+5v_(Input)_79") (pintype "passive"))
      (node (ref "rxPI1") (pin "79") (pinfunction "+5v_(Input)_79") (pintype "passive"))
    )
    (net (code "30") (name "Net-(H1-Pad81)") (class "Default")
      (node (ref "H1") (pin "81") (pinfunction "81_81") (pintype "passive"))
      (node (ref "HA") (pin "82") (pinfunction "82_82") (pintype "passive"))
      (node (ref "rPI1") (pin "81") (pinfunction "+5v_(Input)_81") (pintype "passive"))
      (node (ref "rxPI1") (pin "81") (pinfunction "+5v_(Input)_81") (pintype "passive"))
    )
    (net (code "31") (name "Net-(H1-Pad83)") (class "Default")
      (node (ref "H1") (pin "83") (pinfunction "83_83") (pintype "passive"))
      (node (ref "HA") (pin "84") (pinfunction "84_84") (pintype "passive"))
      (node (ref "rPI1") (pin "83") (pinfunction "+5v_(Input)_83") (pintype "passive"))
      (node (ref "rxPI1") (pin "83") (pinfunction "+5v_(Input)_83") (pintype "passive"))
    )
    (net (code "32") (name "Net-(H1-Pad85)") (class "Default")
      (node (ref "H1") (pin "85") (pinfunction "85_85") (pintype "passive"))
      (node (ref "HA") (pin "86") (pinfunction "86_86") (pintype "passive"))
      (node (ref "rPI1") (pin "85") (pinfunction "+5v_(Input)_85") (pintype "passive"))
      (node (ref "rxPI1") (pin "85") (pinfunction "+5v_(Input)_85") (pintype "passive"))
    )
    (net (code "33") (name "Net-(H1-Pad86)") (class "Default")
      (node (ref "H1") (pin "86") (pinfunction "86_86") (pintype "passive"))
      (node (ref "HA") (pin "85") (pinfunction "85_85") (pintype "passive"))
      (node (ref "rPI1") (pin "86") (pinfunction "+3.3v_(Output)_86") (pintype "passive"))
      (node (ref "rxPI1") (pin "86") (pinfunction "+3.3v_(Output)_86") (pintype "passive"))
    )
    (net (code "34") (name "Net-(H1-Pad87)") (class "Default")
      (node (ref "H1") (pin "87") (pinfunction "87_87") (pintype "passive"))
      (node (ref "HA") (pin "88") (pinfunction "88_88") (pintype "passive"))
      (node (ref "rPI1") (pin "87") (pinfunction "+5v_(Input)_87") (pintype "passive"))
      (node (ref "rxPI1") (pin "87") (pinfunction "+5v_(Input)_87") (pintype "passive"))
    )
    (net (code "35") (name "Net-(H1-Pad88)") (class "Default")
      (node (ref "H1") (pin "88") (pinfunction "88_88") (pintype "passive"))
      (node (ref "HA") (pin "87") (pinfunction "87_87") (pintype "passive"))
      (node (ref "rPI1") (pin "88") (pinfunction "+1.8v_(Output)_88") (pintype "passive"))
      (node (ref "rxPI1") (pin "88") (pinfunction "+1.8v_(Output)_88") (pintype "passive"))
    )
    (net (code "36") (name "Net-(H1-Pad90)") (class "Default")
      (node (ref "H1") (pin "90") (pinfunction "90_90") (pintype "passive"))
      (node (ref "HA") (pin "89") (pinfunction "89_89") (pintype "passive"))
      (node (ref "rPI1") (pin "90") (pinfunction "+1.8v_(Output)_90") (pintype "passive"))
      (node (ref "rxPI1") (pin "90") (pinfunction "+1.8v_(Output)_90") (pintype "passive"))
    )
    (net (code "37") (name "Net-(J3-Pad15)") (class "Default")
      (node (ref "J3") (pin "15") (pinfunction "15_15") (pintype "passive"))
      (node (ref "rxPI1") (pin "216") (pinfunction "nc_216") (pintype "passive"))
    )
    (net (code "38") (name "Net-(J3-Pad34)") (class "Default")
      (node (ref "J3") (pin "34") (pinfunction "34_34") (pintype "passive"))
      (node (ref "rxPI1") (pin "233") (pinfunction "nc_233") (pintype "passive"))
    )
    (net (code "39") (name "Net-(J3-Pad36)") (class "Default")
      (node (ref "J3") (pin "36") (pinfunction "36_36") (pintype "passive"))
      (node (ref "rxPI1") (pin "235") (pinfunction "nc_235") (pintype "passive"))
    )
    (net (code "40") (name "Net-(J3-Pad49)") (class "Default")
      (node (ref "J3") (pin "49") (pinfunction "49_49") (pintype "passive"))
      (node (ref "rxPI1") (pin "250") (pinfunction "nc_250") (pintype "passive"))
    )
    (net (code "41") (name "Net-(J3-Pad51)") (class "Default")
      (node (ref "J3") (pin "51") (pinfunction "51_51") (pintype "passive"))
      (node (ref "rxPI1") (pin "252") (pinfunction "nc_252") (pintype "passive"))
    )
    (net (code "42") (name "Net-(J3-Pad53)") (class "Default")
      (node (ref "J3") (pin "53") (pinfunction "53_53") (pintype "passive"))
      (node (ref "rxPI1") (pin "254") (pinfunction "nc_254") (pintype "passive"))
    )
    (net (code "43") (name "Net-(J3-Pad57)") (class "Default")
      (node (ref "J3") (pin "57") (pinfunction "57_57") (pintype "passive"))
      (node (ref "rxPI1") (pin "258") (pinfunction "nc_258") (pintype "passive"))
    )
    (net (code "44") (name "Net-(J3-Pad59)") (class "Default")
      (node (ref "J3") (pin "59") (pinfunction "59_59") (pintype "passive"))
      (node (ref "rxPI1") (pin "260") (pinfunction "nc_260") (pintype "passive"))
    )
    (net (code "45") (name "Net-(J3-Pad63)") (class "Default")
      (node (ref "J3") (pin "63") (pinfunction "63_63") (pintype "passive"))
      (node (ref "rxPI1") (pin "264") (pinfunction "nc_264") (pintype "passive"))
    )
    (net (code "46") (name "Net-(J3-Pad65)") (class "Default")
      (node (ref "J3") (pin "65") (pinfunction "65_65") (pintype "passive"))
      (node (ref "rxPI1") (pin "266") (pinfunction "nc_266") (pintype "passive"))
    )
    (net (code "47") (name "Net-(J3-Pad69)") (class "Default")
      (node (ref "J3") (pin "69") (pinfunction "69_69") (pintype "passive"))
      (node (ref "rxPI1") (pin "270") (pinfunction "nc_270") (pintype "passive"))
    )
    (net (code "48") (name "Net-(J3-Pad77)") (class "Default")
      (node (ref "J3") (pin "77") (pinfunction "77_77") (pintype "passive"))
      (node (ref "rxPI1") (pin "278") (pinfunction "nc_278") (pintype "passive"))
    )
    (net (code "49") (name "Net-(J3-Pad79)") (class "Default")
      (node (ref "J3") (pin "79") (pinfunction "79_79") (pintype "passive"))
      (node (ref "rxPI1") (pin "280") (pinfunction "nc_280") (pintype "passive"))
    )
    (net (code "50") (name "Net-(J3-Pad81)") (class "Default")
      (node (ref "J3") (pin "81") (pinfunction "81_81") (pintype "passive"))
      (node (ref "rxPI1") (pin "282") (pinfunction "nc_282") (pintype "passive"))
    )
    (net (code "51") (name "Net-(J3-Pad83)") (class "Default")
      (node (ref "J3") (pin "83") (pinfunction "83_83") (pintype "passive"))
      (node (ref "rxPI1") (pin "284") (pinfunction "nc_284") (pintype "passive"))
    )
    (net (code "52") (name "Net-(J3-Pad85)") (class "Default")
      (node (ref "J3") (pin "85") (pinfunction "85_85") (pintype "passive"))
      (node (ref "rxPI1") (pin "286") (pinfunction "nc_286") (pintype "passive"))
    )
    (net (code "53") (name "Net-(J3-Pad87)") (class "Default")
      (node (ref "J3") (pin "87") (pinfunction "87_87") (pintype "passive"))
      (node (ref "rxPI1") (pin "288") (pinfunction "nc_288") (pintype "passive"))
    )
    (net (code "54") (name "Net-(J3-Pad89)") (class "Default")
      (node (ref "J3") (pin "89") (pinfunction "89_89") (pintype "passive"))
      (node (ref "rxPI1") (pin "290") (pinfunction "nc_290") (pintype "passive"))
    )
    (net (code "55") (name "Net-(J3-Pad92)") (class "Default")
      (node (ref "J3") (pin "92") (pinfunction "92_92") (pintype "passive"))
      (node (ref "rxPI1") (pin "291") (pinfunction "nc_291") (pintype "passive"))
    )
    (net (code "56") (name "Net-(U1-OEn)") (class "Default")
      (node (ref "R1") (pin "1") (pinfunction "1_1") (pintype "passive"))
      (node (ref "U1") (pin "2") (pinfunction "OEn_2") (pintype "input"))
    )
    (net (code "57") (name "Net-(rPI1A-BT_nDisable)") (class "Default")
      (node (ref "H1") (pin "91") (pinfunction "91_91") (pintype "passive"))
      (node (ref "HA") (pin "92") (pinfunction "92_92") (pintype "passive"))
      (node (ref "rPI1") (pin "91") (pinfunction "BT_nDisable_91") (pintype "passive"))
      (node (ref "rxPI1") (pin "91") (pinfunction "BT_nDisable_91") (pintype "passive"))
    )
    (net (code "58") (name "Net-(rPI1A-CAM_GPIO1)") (class "Default")
      (node (ref "H1") (pin "100") (pinfunction "100_100") (pintype "passive"))
      (node (ref "HA") (pin "99") (pinfunction "99_99") (pintype "passive"))
      (node (ref "rPI1") (pin "100") (pinfunction "CAM_GPIO1_100") (pintype "passive"))
      (node (ref "rxPI1") (pin "100") (pinfunction "nEXTRST_100") (pintype "passive"))
    )
    (net (code "59") (name "Net-(rPI1A-CC1)") (class "Default")
      (node (ref "H1") (pin "94") (pinfunction "94_94") (pintype "passive"))
      (node (ref "HA") (pin "93") (pinfunction "93_93") (pintype "passive"))
      (node (ref "rPI1") (pin "94") (pinfunction "CC1_94") (pintype "passive"))
      (node (ref "rxPI1") (pin "94") (pinfunction "AnalogIP0_94") (pintype "passive"))
    )
    (net (code "60") (name "Net-(rPI1A-CC2)") (class "Default")
      (node (ref "H1") (pin "96") (pinfunction "96_96") (pintype "passive"))
      (node (ref "HA") (pin "95") (pinfunction "95_95") (pintype "passive"))
      (node (ref "rPI1") (pin "96") (pinfunction "CC2_96") (pintype "passive"))
      (node (ref "rxPI1") (pin "96") (pinfunction "AnalogIP1_96") (pintype "passive"))
    )
    (net (code "61") (name "Net-(rPI1A-Camera_GPIO)") (class "Default")
      (node (ref "H1") (pin "97") (pinfunction "97_97") (pintype "passive"))
      (node (ref "HA") (pin "98") (pinfunction "98_98") (pintype "passive"))
      (node (ref "rPI1") (pin "97") (pinfunction "Camera_GPIO_97") (pintype "passive"))
      (node (ref "rxPI1") (pin "97") (pinfunction "Camera_GPIO_97") (pintype "passive"))
    )
    (net (code "62") (name "Net-(rPI1A-EEPROM_nWP)") (class "Default")
      (node (ref "H1") (pin "20") (pinfunction "20_20") (pintype "passive"))
      (node (ref "HA") (pin "19") (pinfunction "19_19") (pintype "passive"))
      (node (ref "rPI1") (pin "20") (pinfunction "EEPROM_nWP_20") (pintype "passive"))
      (node (ref "rxPI1") (pin "20") (pinfunction "EEPROM_nWP_20") (pintype "passive"))
    )
    (net (code "63") (name "Net-(rPI1A-Ethernet_Pair0_N)") (class "Default")
      (node (ref "H1") (pin "10") (pinfunction "10_10") (pintype "passive"))
      (node (ref "HA") (pin "9") (pinfunction "9_9") (pintype "passive"))
      (node (ref "rPI1") (pin "10") (pinfunction "Ethernet_Pair0_N_10") (pintype "passive"))
      (node (ref "rxPI1") (pin "10") (pinfunction "Ethernet_Pair0_N_10") (pintype "passive"))
    )
    (net (code "64") (name "Net-(rPI1A-Ethernet_Pair0_P)") (class "Default")
      (node (ref "H1") (pin "12") (pinfunction "12_12") (pintype "passive"))
      (node (ref "HA") (pin "11") (pinfunction "11_11") (pintype "passive"))
      (node (ref "rPI1") (pin "12") (pinfunction "Ethernet_Pair0_P_12") (pintype "passive"))
      (node (ref "rxPI1") (pin "12") (pinfunction "Ethernet_Pair0_P_12") (pintype "passive"))
    )
    (net (code "65") (name "Net-(rPI1A-Ethernet_Pair1_N)") (class "Default")
      (node (ref "H1") (pin "6") (pinfunction "6_6") (pintype "passive"))
      (node (ref "HA") (pin "5") (pinfunction "5_5") (pintype "passive"))
      (node (ref "rPI1") (pin "6") (pinfunction "Ethernet_Pair1_N_6") (pintype "passive"))
      (node (ref "rxPI1") (pin "6") (pinfunction "Ethernet_Pair1_N_6") (pintype "passive"))
    )
    (net (code "66") (name "Net-(rPI1A-Ethernet_Pair1_P)") (class "Default")
      (node (ref "H1") (pin "4") (pinfunction "4_4") (pintype "passive"))
      (node (ref "HA") (pin "3") (pinfunction "3_3") (pintype "passive"))
      (node (ref "rPI1") (pin "4") (pinfunction "Ethernet_Pair1_P_4") (pintype "passive"))
      (node (ref "rxPI1") (pin "4") (pinfunction "Ethernet_Pair1_P_4") (pintype "passive"))
    )
    (net (code "67") (name "Net-(rPI1A-Ethernet_Pair2_N)") (class "Default")
      (node (ref "H1") (pin "9") (pinfunction "9_9") (pintype "passive"))
      (node (ref "HA") (pin "10") (pinfunction "10_10") (pintype "passive"))
      (node (ref "rPI1") (pin "9") (pinfunction "Ethernet_Pair2_N_9") (pintype "passive"))
      (node (ref "rxPI1") (pin "9") (pinfunction "Ethernet_Pair2_N_9") (pintype "passive"))
    )
    (net (code "68") (name "Net-(rPI1A-Ethernet_Pair2_P)") (class "Default")
      (node (ref "H1") (pin "11") (pinfunction "11_11") (pintype "passive"))
      (node (ref "HA") (pin "12") (pinfunction "12_12") (pintype "passive"))
      (node (ref "rPI1") (pin "11") (pinfunction "Ethernet_Pair2_P_11") (pintype "passive"))
      (node (ref "rxPI1") (pin "11") (pinfunction "Ethernet_Pair2_P_11") (pintype "passive"))
    )
    (net (code "69") (name "Net-(rPI1A-Ethernet_Pair3_N)") (class "Default")
      (node (ref "H1") (pin "5") (pinfunction "5_5") (pintype "passive"))
      (node (ref "HA") (pin "6") (pinfunction "6_6") (pintype "passive"))
      (node (ref "rPI1") (pin "5") (pinfunction "Ethernet_Pair3_N_5") (pintype "passive"))
      (node (ref "rxPI1") (pin "5") (pinfunction "Ethernet_Pair3_N_5") (pintype "passive"))
    )
    (net (code "70") (name "Net-(rPI1A-Ethernet_Pair3_P)") (class "Default")
      (node (ref "H1") (pin "3") (pinfunction "3_3") (pintype "passive"))
      (node (ref "HA") (pin "4") (pinfunction "4_4") (pintype "passive"))
      (node (ref "rPI1") (pin "3") (pinfunction "Ethernet_Pair3_P_3") (pintype "passive"))
      (node (ref "rxPI1") (pin "3") (pinfunction "Ethernet_Pair3_P_3") (pintype "passive"))
    )
    (net (code "71") (name "Net-(rPI1A-Ethernet_SYNC_IN(1.8v))") (class "Default")
      (node (ref "H1") (pin "16") (pinfunction "16_16") (pintype "passive"))
      (node (ref "HA") (pin "15") (pinfunction "15_15") (pintype "passive"))
      (node (ref "rPI1") (pin "16") (pinfunction "Ethernet_SYNC_IN(1.8v)_16") (pintype "passive"))
      (node (ref "rxPI1") (pin "16") (pinfunction "Ethernet_SYNC_IN(1.8v)_16") (pintype "passive"))
    )
    (net (code "72") (name "Net-(rPI1A-Ethernet_SYNC_OUT(1.8v))") (class "Default")
      (node (ref "H1") (pin "18") (pinfunction "18_18") (pintype "passive"))
      (node (ref "HA") (pin "17") (pinfunction "17_17") (pintype "passive"))
      (node (ref "rPI1") (pin "18") (pinfunction "Ethernet_SYNC_OUT(1.8v)_18") (pintype "passive"))
      (node (ref "rxPI1") (pin "18") (pinfunction "Ethernet_SYNC_OUT(1.8v)_18") (pintype "passive"))
    )
    (net (code "73") (name "Net-(rPI1A-Ethernet_nLED2(3.3v))") (class "Default")
      (node (ref "H1") (pin "17") (pinfunction "17_17") (pintype "passive"))
      (node (ref "HA") (pin "18") (pinfunction "18_18") (pintype "passive"))
      (node (ref "rPI1") (pin "17") (pinfunction "Ethernet_nLED2(3.3v)_17") (pintype "passive"))
      (node (ref "rxPI1") (pin "17") (pinfunction "Ethernet_nLED2(3.3v)_17") (pintype "passive"))
    )
    (net (code "74") (name "Net-(rPI1A-Ethernet_nLED3(3.3v))") (class "Default")
      (node (ref "H1") (pin "15") (pinfunction "15_15") (pintype "passive"))
      (node (ref "HA") (pin "16") (pinfunction "16_16") (pintype "passive"))
      (node (ref "rPI1") (pin "15") (pinfunction "Ethernet_nLED3(3.3v)_15") (pintype "passive"))
      (node (ref "rxPI1") (pin "15") (pinfunction "Ethernet_nLED3(3.3v)_15") (pintype "passive"))
    )
    (net (code "75") (name "Net-(rPI1A-FAN_PWM)") (class "Default")
      (node (ref "H1") (pin "19") (pinfunction "19_19") (pintype "passive"))
      (node (ref "HA") (pin "20") (pinfunction "20_20") (pintype "passive"))
      (node (ref "rPI1") (pin "19") (pinfunction "FAN_PWM_19") (pintype "passive"))
      (node (ref "rxPI1") (pin "19") (pinfunction "Ethernet_nLED1(3.3v)_19") (pintype "passive"))
    )
    (net (code "76") (name "Net-(rPI1A-GPIO2)") (class "Default")
      (node (ref "H1") (pin "58") (pinfunction "58_58") (pintype "passive"))
      (node (ref "HA") (pin "57") (pinfunction "57_57") (pintype "passive"))
      (node (ref "rPI1") (pin "58") (pinfunction "GPIO2_58") (pintype "passive"))
      (node (ref "rxPI1") (pin "58") (pinfunction "GPIO2_58") (pintype "passive"))
    )
    (net (code "77") (name "Net-(rPI1A-GPIO3)") (class "Default")
      (node (ref "H1") (pin "56") (pinfunction "56_56") (pintype "passive"))
      (node (ref "HA") (pin "55") (pinfunction "55_55") (pintype "passive"))
      (node (ref "rPI1") (pin "56") (pinfunction "GPIO3_56") (pintype "passive"))
      (node (ref "rxPI1") (pin "56") (pinfunction "GPIO3_56") (pintype "passive"))
    )
    (net (code "78") (name "Net-(rPI1A-GPIO4)") (class "Default")
      (node (ref "H1") (pin "54") (pinfunction "54_54") (pintype "passive"))
      (node (ref "HA") (pin "53") (pinfunction "53_53") (pintype "passive"))
      (node (ref "rPI1") (pin "54") (pinfunction "GPIO4_54") (pintype "passive"))
      (node (ref "rxPI1") (pin "54") (pinfunction "GPIO4_54") (pintype "passive"))
    )
    (net (code "79") (name "Net-(rPI1A-GPIO5)") (class "Default")
      (node (ref "H1") (pin "34") (pinfunction "34_34") (pintype "passive"))
      (node (ref "HA") (pin "33") (pinfunction "33_33") (pintype "passive"))
      (node (ref "rPI1") (pin "34") (pinfunction "GPIO5_34") (pintype "passive"))
      (node (ref "rxPI1") (pin "34") (pinfunction "GPIO5_34") (pintype "passive"))
    )
    (net (code "80") (name "Net-(rPI1A-GPIO6)") (class "Default")
      (node (ref "H1") (pin "30") (pinfunction "30_30") (pintype "passive"))
      (node (ref "HA") (pin "29") (pinfunction "29_29") (pintype "passive"))
      (node (ref "rPI1") (pin "30") (pinfunction "GPIO6_30") (pintype "passive"))
      (node (ref "rxPI1") (pin "30") (pinfunction "GPIO6_30") (pintype "passive"))
    )
    (net (code "81") (name "Net-(rPI1A-GPIO7)") (class "Default")
      (node (ref "H1") (pin "37") (pinfunction "37_37") (pintype "passive"))
      (node (ref "HA") (pin "38") (pinfunction "38_38") (pintype "passive"))
      (node (ref "rPI1") (pin "37") (pinfunction "GPIO7_37") (pintype "passive"))
      (node (ref "rxPI1") (pin "37") (pinfunction "GPIO7_37") (pintype "passive"))
    )
    (net (code "82") (name "Net-(rPI1A-GPIO8)") (class "Default")
      (node (ref "H1") (pin "39") (pinfunction "39_39") (pintype "passive"))
      (node (ref "HA") (pin "40") (pinfunction "40_40") (pintype "passive"))
      (node (ref "rPI1") (pin "39") (pinfunction "GPIO8_39") (pintype "passive"))
      (node (ref "rxPI1") (pin "39") (pinfunction "GPIO8_39") (pintype "passive"))
    )
    (net (code "83") (name "Net-(rPI1A-GPIO9)") (class "Default")
      (node (ref "H1") (pin "40") (pinfunction "40_40") (pintype "passive"))
      (node (ref "HA") (pin "39") (pinfunction "39_39") (pintype "passive"))
      (node (ref "rPI1") (pin "40") (pinfunction "GPIO9_40") (pintype "passive"))
      (node (ref "rxPI1") (pin "40") (pinfunction "GPIO9_40") (pintype "passive"))
    )
    (net (code "84") (name "Net-(rPI1A-GPIO10)") (class "Default")
      (node (ref "H1") (pin "44") (pinfunction "44_44") (pintype "passive"))
      (node (ref "HA") (pin "43") (pinfunction "43_43") (pintype "passive"))
      (node (ref "rPI1") (pin "44") (pinfunction "GPIO10_44") (pintype "passive"))
      (node (ref "rxPI1") (pin "44") (pinfunction "GPIO10_44") (pintype "passive"))
    )
    (net (code "85") (name "Net-(rPI1A-GPIO11)") (class "Default")
      (node (ref "H1") (pin "38") (pinfunction "38_38") (pintype "passive"))
      (node (ref "HA") (pin "37") (pinfunction "37_37") (pintype "passive"))
      (node (ref "rPI1") (pin "38") (pinfunction "GPIO11_38") (pintype "passive"))
      (node (ref "rxPI1") (pin "38") (pinfunction "GPIO11_38") (pintype "passive"))
    )
    (net (code "86") (name "Net-(rPI1A-GPIO12)") (class "Default")
      (node (ref "H1") (pin "31") (pinfunction "31_31") (pintype "passive"))
      (node (ref "HA") (pin "32") (pinfunction "32_32") (pintype "passive"))
      (node (ref "rPI1") (pin "31") (pinfunction "GPIO12_31") (pintype "passive"))
      (node (ref "rxPI1") (pin "31") (pinfunction "GPIO12_31") (pintype "passive"))
    )
    (net (code "87") (name "Net-(rPI1A-GPIO13)") (class "Default")
      (node (ref "H1") (pin "28") (pinfunction "28_28") (pintype "passive"))
      (node (ref "HA") (pin "27") (pinfunction "27_27") (pintype "passive"))
      (node (ref "rPI1") (pin "28") (pinfunction "GPIO13_28") (pintype "passive"))
      (node (ref "rxPI1") (pin "28") (pinfunction "GPIO13_28") (pintype "passive"))
    )
    (net (code "88") (name "Net-(rPI1A-GPIO14)") (class "Default")
      (node (ref "H1") (pin "55") (pinfunction "55_55") (pintype "passive"))
      (node (ref "HA") (pin "56") (pinfunction "56_56") (pintype "passive"))
      (node (ref "rPI1") (pin "55") (pinfunction "GPIO14_55") (pintype "passive"))
      (node (ref "rxPI1") (pin "55") (pinfunction "GPIO14_55") (pintype "passive"))
    )
    (net (code "89") (name "Net-(rPI1A-GPIO15)") (class "Default")
      (node (ref "H1") (pin "51") (pinfunction "51_51") (pintype "passive"))
      (node (ref "HA") (pin "52") (pinfunction "52_52") (pintype "passive"))
      (node (ref "rPI1") (pin "51") (pinfunction "GPIO15_51") (pintype "passive"))
      (node (ref "rxPI1") (pin "51") (pinfunction "GPIO15_51") (pintype "passive"))
    )
    (net (code "90") (name "Net-(rPI1A-GPIO16)") (class "Default")
      (node (ref "H1") (pin "29") (pinfunction "29_29") (pintype "passive"))
      (node (ref "HA") (pin "30") (pinfunction "30_30") (pintype "passive"))
      (node (ref "rPI1") (pin "29") (pinfunction "GPIO16_29") (pintype "passive"))
      (node (ref "rxPI1") (pin "29") (pinfunction "GPIO16_29") (pintype "passive"))
    )
    (net (code "91") (name "Net-(rPI1A-GPIO17)") (class "Default")
      (node (ref "H1") (pin "50") (pinfunction "50_50") (pintype "passive"))
      (node (ref "HA") (pin "49") (pinfunction "49_49") (pintype "passive"))
      (node (ref "rPI1") (pin "50") (pinfunction "GPIO17_50") (pintype "passive"))
      (node (ref "rxPI1") (pin "50") (pinfunction "GPIO17_50") (pintype "passive"))
    )
    (net (code "92") (name "Net-(rPI1A-GPIO18)") (class "Default")
      (node (ref "H1") (pin "49") (pinfunction "49_49") (pintype "passive"))
      (node (ref "HA") (pin "50") (pinfunction "50_50") (pintype "passive"))
      (node (ref "rPI1") (pin "49") (pinfunction "GPIO18_49") (pintype "passive"))
      (node (ref "rxPI1") (pin "49") (pinfunction "GPIO18_49") (pintype "passive"))
    )
    (net (code "93") (name "Net-(rPI1A-GPIO19)") (class "Default")
      (node (ref "H1") (pin "26") (pinfunction "26_26") (pintype "passive"))
      (node (ref "HA") (pin "25") (pinfunction "25_25") (pintype "passive"))
      (node (ref "rPI1") (pin "26") (pinfunction "GPIO19_26") (pintype "passive"))
      (node (ref "rxPI1") (pin "26") (pinfunction "GPIO19_26") (pintype "passive"))
    )
    (net (code "94") (name "Net-(rPI1A-GPIO20)") (class "Default")
      (node (ref "H1") (pin "27") (pinfunction "27_27") (pintype "passive"))
      (node (ref "HA") (pin "28") (pinfunction "28_28") (pintype "passive"))
      (node (ref "rPI1") (pin "27") (pinfunction "GPIO20_27") (pintype "passive"))
      (node (ref "rxPI1") (pin "27") (pinfunction "GPIO20_27") (pintype "passive"))
    )
    (net (code "95") (name "Net-(rPI1A-GPIO21)") (class "Default")
      (node (ref "H1") (pin "25") (pinfunction "25_25") (pintype "passive"))
      (node (ref "HA") (pin "26") (pinfunction "26_26") (pintype "passive"))
      (node (ref "rPI1") (pin "25") (pinfunction "GPIO21_25") (pintype "passive"))
      (node (ref "rxPI1") (pin "25") (pinfunction "GPIO21_25") (pintype "passive"))
    )
    (net (code "96") (name "Net-(rPI1A-GPIO22)") (class "Default")
      (node (ref "H1") (pin "46") (pinfunction "46_46") (pintype "passive"))
      (node (ref "HA") (pin "45") (pinfunction "45_45") (pintype "passive"))
      (node (ref "rPI1") (pin "46") (pinfunction "GPIO22_46") (pintype "passive"))
      (node (ref "rxPI1") (pin "46") (pinfunction "GPIO22_46") (pintype "passive"))
    )
    (net (code "97") (name "Net-(rPI1A-GPIO23)") (class "Default")
      (node (ref "H1") (pin "47") (pinfunction "47_47") (pintype "passive"))
      (node (ref "HA") (pin "48") (pinfunction "48_48") (pintype "passive"))
      (node (ref "rPI1") (pin "47") (pinfunction "GPIO23_47") (pintype "passive"))
      (node (ref "rxPI1") (pin "47") (pinfunction "GPIO23_47") (pintype "passive"))
    )
    (net (code "98") (name "Net-(rPI1A-GPIO24)") (class "Default")
      (node (ref "H1") (pin "45") (pinfunction "45_45") (pintype "passive"))
      (node (ref "HA") (pin "46") (pinfunction "46_46") (pintype "passive"))
      (node (ref "rPI1") (pin "45") (pinfunction "GPIO24_45") (pintype "passive"))
      (node (ref "rxPI1") (pin "45") (pinfunction "GPIO24_45") (pintype "passive"))
    )
    (net (code "99") (name "Net-(rPI1A-GPIO25)") (class "Default")
      (node (ref "H1") (pin "41") (pinfunction "41_41") (pintype "passive"))
      (node (ref "HA") (pin "42") (pinfunction "42_42") (pintype "passive"))
      (node (ref "rPI1") (pin "41") (pinfunction "GPIO25_41") (pintype "passive"))
      (node (ref "rxPI1") (pin "41") (pinfunction "GPIO25_41") (pintype "passive"))
    )
    (net (code "100") (name "Net-(rPI1A-GPIO26)") (class "Default")
      (node (ref "H1") (pin "24") (pinfunction "24_24") (pintype "passive"))
      (node (ref "HA") (pin "23") (pinfunction "23_23") (pintype "passive"))
      (node (ref "rPI1") (pin "24") (pinfunction "GPIO26_24") (pintype "passive"))
      (node (ref "rxPI1") (pin "24") (pinfunction "GPIO26_24") (pintype "passive"))
    )
    (net (code "101") (name "Net-(rPI1A-GPIO27)") (class "Default")
      (node (ref "H1") (pin "48") (pinfunction "48_48") (pintype "passive"))
      (node (ref "HA") (pin "47") (pinfunction "47_47") (pintype "passive"))
      (node (ref "rPI1") (pin "48") (pinfunction "GPIO27_48") (pintype "passive"))
      (node (ref "rxPI1") (pin "48") (pinfunction "GPIO27_48") (pintype "passive"))
    )
    (net (code "102") (name "Net-(rPI1A-GPIO_VREF(1.8v{slash}3.3v_Input))") (class "Default")
      (node (ref "H1") (pin "78") (pinfunction "78_78") (pintype "passive"))
      (node (ref "HA") (pin "77") (pinfunction "77_77") (pintype "passive"))
      (node (ref "rPI1") (pin "78") (pinfunction "GPIO_VREF(1.8v/3.3v_Input)_78") (pintype "passive"))
      (node (ref "rxPI1") (pin "78") (pinfunction "GPIO_VREF(1.8v/3.3v_Input)_78") (pintype "passive"))
    )
    (net (code "103") (name "Net-(rPI1A-Global_EN)") (class "Default")
      (node (ref "H1") (pin "99") (pinfunction "99_99") (pintype "passive"))
      (node (ref "HA") (pin "100") (pinfunction "100_100") (pintype "passive"))
      (node (ref "rPI1") (pin "99") (pinfunction "Global_EN_99") (pintype "passive"))
      (node (ref "rxPI1") (pin "99") (pinfunction "Global_EN_99") (pintype "passive"))
    )
    (net (code "104") (name "Net-(rPI1A-ID_SC)") (class "Default")
      (node (ref "H1") (pin "35") (pinfunction "35_35") (pintype "passive"))
      (node (ref "HA") (pin "36") (pinfunction "36_36") (pintype "passive"))
      (node (ref "rPI1") (pin "35") (pinfunction "ID_SC_35") (pintype "passive"))
      (node (ref "rxPI1") (pin "35") (pinfunction "ID_SC_35") (pintype "passive"))
    )
    (net (code "105") (name "Net-(rPI1A-ID_SD)") (class "Default")
      (node (ref "H1") (pin "36") (pinfunction "36_36") (pintype "passive"))
      (node (ref "HA") (pin "35") (pinfunction "35_35") (pintype "passive"))
      (node (ref "rPI1") (pin "36") (pinfunction "ID_SD_36") (pintype "passive"))
      (node (ref "rxPI1") (pin "36") (pinfunction "ID_SD_36") (pintype "passive"))
    )
    (net (code "106") (name "Net-(rPI1A-PI_nLED_Activity)") (class "Default")
      (node (ref "H1") (pin "21") (pinfunction "21_21") (pintype "passive"))
      (node (ref "HA") (pin "22") (pinfunction "22_22") (pintype "passive"))
      (node (ref "rPI1") (pin "21") (pinfunction "PI_nLED_Activity_21") (pintype "passive"))
      (node (ref "rxPI1") (pin "21") (pinfunction "PI_nLED_Activity_21") (pintype "passive"))
    )
    (net (code "107") (name "Net-(rPI1A-RUN_PG)") (class "Default")
      (node (ref "H1") (pin "92") (pinfunction "92_92") (pintype "passive"))
      (node (ref "HA") (pin "91") (pinfunction "91_91") (pintype "passive"))
      (node (ref "rPI1") (pin "92") (pinfunction "RUN_PG_92") (pintype "passive"))
      (node (ref "rxPI1") (pin "92") (pinfunction "RUN_PG_92") (pintype "passive"))
    )
    (net (code "108") (name "Net-(rPI1A-Reserved)") (class "Default")
      (node (ref "H1") (pin "76") (pinfunction "76_76") (pintype "passive"))
      (node (ref "HA") (pin "75") (pinfunction "75_75") (pintype "passive"))
      (node (ref "rPI1") (pin "76") (pinfunction "Reserved_76") (pintype "passive"))
      (node (ref "rxPI1") (pin "76") (pinfunction "Reserved_76") (pintype "passive"))
    )
    (net (code "109") (name "Net-(rPI1A-SCL0)") (class "Default")
      (node (ref "H1") (pin "80") (pinfunction "80_80") (pintype "passive"))
      (node (ref "HA") (pin "79") (pinfunction "79_79") (pintype "passive"))
      (node (ref "rPI1") (pin "80") (pinfunction "SCL0_80") (pintype "passive"))
      (node (ref "rxPI1") (pin "80") (pinfunction "SCL0_80") (pintype "passive"))
    )
    (net (code "110") (name "Net-(rPI1A-SDA0)") (class "Default")
      (node (ref "H1") (pin "82") (pinfunction "82_82") (pintype "passive"))
      (node (ref "HA") (pin "81") (pinfunction "81_81") (pintype "passive"))
      (node (ref "rPI1") (pin "82") (pinfunction "SDA0_82") (pintype "passive"))
      (node (ref "rxPI1") (pin "82") (pinfunction "SDA0_82") (pintype "passive"))
    )
    (net (code "111") (name "Net-(rPI1A-SD_CLK)") (class "Default")
      (node (ref "H1") (pin "57") (pinfunction "57_57") (pintype "passive"))
      (node (ref "HA") (pin "58") (pinfunction "58_58") (pintype "passive"))
      (node (ref "rPI1") (pin "57") (pinfunction "SD_CLK_57") (pintype "passive"))
      (node (ref "rxPI1") (pin "57") (pinfunction "SD_CLK_57") (pintype "passive"))
    )
    (net (code "112") (name "Net-(rPI1A-SD_CMD)") (class "Default")
      (node (ref "H1") (pin "62") (pinfunction "62_62") (pintype "passive"))
      (node (ref "HA") (pin "61") (pinfunction "61_61") (pintype "passive"))
      (node (ref "rPI1") (pin "62") (pinfunction "SD_CMD_62") (pintype "passive"))
      (node (ref "rxPI1") (pin "62") (pinfunction "SD_CMD_62") (pintype "passive"))
    )
    (net (code "113") (name "Net-(rPI1A-SD_DAT0)") (class "Default")
      (node (ref "H1") (pin "63") (pinfunction "63_63") (pintype "passive"))
      (node (ref "HA") (pin "64") (pinfunction "64_64") (pintype "passive"))
      (node (ref "rPI1") (pin "63") (pinfunction "SD_DAT0_63") (pintype "passive"))
      (node (ref "rxPI1") (pin "63") (pinfunction "SD_DAT0_63") (pintype "passive"))
    )
    (net (code "114") (name "Net-(rPI1A-SD_DAT1)") (class "Default")
      (node (ref "H1") (pin "67") (pinfunction "67_67") (pintype "passive"))
      (node (ref "HA") (pin "68") (pinfunction "68_68") (pintype "passive"))
      (node (ref "rPI1") (pin "67") (pinfunction "SD_DAT1_67") (pintype "passive"))
      (node (ref "rxPI1") (pin "67") (pinfunction "SD_DAT1_67") (pintype "passive"))
    )
    (net (code "115") (name "Net-(rPI1A-SD_DAT2)") (class "Default")
      (node (ref "H1") (pin "69") (pinfunction "69_69") (pintype "passive"))
      (node (ref "HA") (pin "70") (pinfunction "70_70") (pintype "passive"))
      (node (ref "rPI1") (pin "69") (pinfunction "SD_DAT2_69") (pintype "passive"))
      (node (ref "rxPI1") (pin "69") (pinfunction "SD_DAT2_69") (pintype "passive"))
    )
    (net (code "116") (name "Net-(rPI1A-SD_DAT3)") (class "Default")
      (node (ref "H1") (pin "61") (pinfunction "61_61") (pintype "passive"))
      (node (ref "HA") (pin "62") (pinfunction "62_62") (pintype "passive"))
      (node (ref "rPI1") (pin "61") (pinfunction "SD_DAT3_61") (pintype "passive"))
      (node (ref "rxPI1") (pin "61") (pinfunction "SD_DAT3_61") (pintype "passive"))
    )
    (net (code "117") (name "Net-(rPI1A-SD_DAT4)") (class "Default")
      (node (ref "H1") (pin "68") (pinfunction "68_68") (pintype "passive"))
      (node (ref "HA") (pin "67") (pinfunction "67_67") (pintype "passive"))
      (node (ref "rPI1") (pin "68") (pinfunction "SD_DAT4_68") (pintype "passive"))
      (node (ref "rxPI1") (pin "68") (pinfunction "SD_DAT4_68") (pintype "passive"))
    )
    (net (code "118") (name "Net-(rPI1A-SD_DAT5)") (class "Default")
      (node (ref "H1") (pin "64") (pinfunction "64_64") (pintype "passive"))
      (node (ref "HA") (pin "63") (pinfunction "63_63") (pintype "passive"))
      (node (ref "rPI1") (pin "64") (pinfunction "SD_DAT5_64") (pintype "passive"))
      (node (ref "rxPI1") (pin "64") (pinfunction "SD_DAT5_64") (pintype "passive"))
    )
    (net (code "119") (name "Net-(rPI1A-SD_DAT6)") (class "Default")
      (node (ref "H1") (pin "72") (pinfunction "72_72") (pintype "passive"))
      (node (ref "HA") (pin "71") (pinfunction "71_71") (pintype "passive"))
      (node (ref "rPI1") (pin "72") (pinfunction "SD_DAT6_72") (pintype "passive"))
      (node (ref "rxPI1") (pin "72") (pinfunction "SD_DAT6_72") (pintype "passive"))
    )
    (net (code "120") (name "Net-(rPI1A-SD_DAT7)") (class "Default")
      (node (ref "H1") (pin "70") (pinfunction "70_70") (pintype "passive"))
      (node (ref "HA") (pin "69") (pinfunction "69_69") (pintype "passive"))
      (node (ref "rPI1") (pin "70") (pinfunction "SD_DAT7_70") (pintype "passive"))
      (node (ref "rxPI1") (pin "70") (pinfunction "SD_DAT7_70") (pintype "passive"))
    )
    (net (code "121") (name "Net-(rPI1A-SD_PWR_ON)") (class "Default")
      (node (ref "H1") (pin "75") (pinfunction "75_75") (pintype "passive"))
      (node (ref "HA") (pin "76") (pinfunction "76_76") (pintype "passive"))
      (node (ref "rPI1") (pin "75") (pinfunction "SD_PWR_ON_75") (pintype "passive"))
      (node (ref "rxPI1") (pin "75") (pinfunction "SD_PWR_ON_75") (pintype "passive"))
    )
    (net (code "122") (name "Net-(rPI1A-SD_VDD_Override)") (class "Default")
      (node (ref "H1") (pin "73") (pinfunction "73_73") (pintype "passive"))
      (node (ref "HA") (pin "74") (pinfunction "74_74") (pintype "passive"))
      (node (ref "rPI1") (pin "73") (pinfunction "SD_VDD_Override_73") (pintype "passive"))
      (node (ref "rxPI1") (pin "73") (pinfunction "SD_VDD_Override_73") (pintype "passive"))
    )
    (net (code "123") (name "Net-(rPI1A-WiFi_nDisable)") (class "Default")
      (node (ref "H1") (pin "89") (pinfunction "89_89") (pintype "passive"))
      (node (ref "HA") (pin "90") (pinfunction "90_90") (pintype "passive"))
      (node (ref "rPI1") (pin "89") (pinfunction "WiFi_nDisable_89") (pintype "passive"))
      (node (ref "rxPI1") (pin "89") (pinfunction "WiFi_nDisable_89") (pintype "passive"))
    )
    (net (code "124") (name "Net-(rPI1A-nPI_LED_PWR)") (class "Default")
      (node (ref "H1") (pin "95") (pinfunction "95_95") (pintype "passive"))
      (node (ref "HA") (pin "96") (pinfunction "96_96") (pintype "passive"))
      (node (ref "rPI1") (pin "95") (pinfunction "nPI_LED_PWR_95") (pintype "passive"))
      (node (ref "rxPI1") (pin "95") (pinfunction "nPI_LED_PWR_95") (pintype "passive"))
    )
    (net (code "125") (name "Net-(rPI1A-nRPIBOOT)") (class "Default")
      (node (ref "H1") (pin "93") (pinfunction "93_93") (pintype "passive"))
      (node (ref "HA") (pin "94") (pinfunction "94_94") (pintype "passive"))
      (node (ref "rPI1") (pin "93") (pinfunction "nRPIBOOT_93") (pintype "passive"))
      (node (ref "rxPI1") (pin "93") (pinfunction "nRPIBOOT_93") (pintype "passive"))
    )
    (net (code "126") (name "Net-(rPI1B-MIPI0_C_N)") (class "Default")
      (node (ref "HB") (pin "28") (pinfunction "28_28") (pintype "passive"))
      (node (ref "rPI1") (pin "127") (pinfunction "MIPI0_C_N_127") (pintype "passive"))
    )
    (net (code "127") (name "Net-(rPI1B-MIPI0_C_P)") (class "Default")
      (node (ref "HB") (pin "30") (pinfunction "30_30") (pintype "passive"))
      (node (ref "rPI1") (pin "129") (pinfunction "MIPI0_C_P_129") (pintype "passive"))
    )
    (net (code "128") (name "Net-(rPI1B-MIPI0_D0_N)") (class "Default")
      (node (ref "HB") (pin "16") (pinfunction "16_16") (pintype "passive"))
      (node (ref "rPI1") (pin "115") (pinfunction "MIPI0_D0_N_115") (pintype "passive"))
    )
    (net (code "129") (name "Net-(rPI1B-MIPI0_D0_P)") (class "Default")
      (node (ref "HB") (pin "18") (pinfunction "18_18") (pintype "passive"))
      (node (ref "rPI1") (pin "117") (pinfunction "MIPI0_D0_P_117") (pintype "passive"))
    )
    (net (code "130") (name "Net-(rPI1B-MIPI0_D1_N)") (class "Default")
      (node (ref "HB") (pin "22") (pinfunction "22_22") (pintype "passive"))
      (node (ref "rPI1") (pin "121") (pinfunction "MIPI0_D1_N_121") (pintype "passive"))
    )
    (net (code "131") (name "Net-(rPI1B-MIPI0_D1_P)") (class "Default")
      (node (ref "HB") (pin "24") (pinfunction "24_24") (pintype "passive"))
      (node (ref "rPI1") (pin "123") (pinfunction "MIPI0_D1_P_123") (pintype "passive"))
    )
    (net (code "132") (name "Net-(rPI1B-MIPI0_D2_N)") (class "Default")
      (node (ref "HB") (pin "34") (pinfunction "34_34") (pintype "passive"))
      (node (ref "rPI1") (pin "133") (pinfunction "MIPI0_D2_N_133") (pintype "passive"))
    )
    (net (code "133") (name "Net-(rPI1B-MIPI0_D2_P)") (class "Default")
      (node (ref "HB") (pin "36") (pinfunction "36_36") (pintype "passive"))
      (node (ref "rPI1") (pin "135") (pinfunction "MIPI0_D2_P_135") (pintype "passive"))
    )
    (net (code "134") (name "Net-(rPI1B-MIPI0_D3_N)") (class "Default")
      (node (ref "HB") (pin "40") (pinfunction "40_40") (pintype "passive"))
      (node (ref "rPI1") (pin "139") (pinfunction "MIPI0_D3_N_139") (pintype "passive"))
    )
    (net (code "135") (name "Net-(rPI1B-MIPI0_D3_P)") (class "Default")
      (node (ref "HB") (pin "42") (pinfunction "42_42") (pintype "passive"))
      (node (ref "rPI1") (pin "141") (pinfunction "MIPI0_D3_P_141") (pintype "passive"))
    )
    (net (code "136") (name "Net-(rPI1B-MIPI1_C_N)") (class "Default")
      (node (ref "HB") (pin "88") (pinfunction "88_88") (pintype "passive"))
      (node (ref "rPI1") (pin "187") (pinfunction "MIPI1_C_N_187") (pintype "passive"))
    )
    (net (code "137") (name "Net-(rPI1B-MIPI1_C_P)") (class "Default")
      (node (ref "HB") (pin "90") (pinfunction "90_90") (pintype "passive"))
      (node (ref "rPI1") (pin "189") (pinfunction "MIPI1_C_P_189") (pintype "passive"))
    )
    (net (code "138") (name "Net-(rPI1B-MIPI1_D0_N)") (class "Default")
      (node (ref "HB") (pin "76") (pinfunction "76_76") (pintype "passive"))
      (node (ref "rPI1") (pin "175") (pinfunction "MIPI1_D0_N_175") (pintype "passive"))
    )
    (net (code "139") (name "Net-(rPI1B-MIPI1_D0_P)") (class "Default")
      (node (ref "HB") (pin "78") (pinfunction "78_78") (pintype "passive"))
      (node (ref "rPI1") (pin "177") (pinfunction "MIPI1_D0_P_177") (pintype "passive"))
    )
    (net (code "140") (name "Net-(rPI1B-MIPI1_D1_N)") (class "Default")
      (node (ref "HB") (pin "82") (pinfunction "82_82") (pintype "passive"))
      (node (ref "rPI1") (pin "181") (pinfunction "MIPI1_D1_N_181") (pintype "passive"))
    )
    (net (code "141") (name "Net-(rPI1B-MIPI1_D1_P)") (class "Default")
      (node (ref "HB") (pin "84") (pinfunction "84_84") (pintype "passive"))
      (node (ref "rPI1") (pin "183") (pinfunction "MIPI1_D1_P_183") (pintype "passive"))
    )
    (net (code "142") (name "Net-(rPI1B-MIPI1_D2_N)") (class "Default")
      (node (ref "HB") (pin "94") (pinfunction "94_94") (pintype "passive"))
      (node (ref "rPI1") (pin "193") (pinfunction "MIPI1_D2_N_193") (pintype "passive"))
    )
    (net (code "143") (name "Net-(rPI1B-MIPI1_D2_P)") (class "Default")
      (node (ref "HB") (pin "96") (pinfunction "96_96") (pintype "passive"))
      (node (ref "rPI1") (pin "195") (pinfunction "MIPI1_D2_P_195") (pintype "passive"))
    )
    (net (code "144") (name "Net-(rPI1B-MIPI1_D3_N)") (class "Default")
      (node (ref "HB") (pin "93") (pinfunction "93_93") (pintype "passive"))
      (node (ref "rPI1") (pin "194") (pinfunction "MIPI1_D3_N_194") (pintype "passive"))
    )
    (net (code "145") (name "Net-(rPI1B-MIPI1_D3_P)") (class "Default")
      (node (ref "HB") (pin "95") (pinfunction "95_95") (pintype "passive"))
      (node (ref "rPI1") (pin "196") (pinfunction "MIPI1_D3_P_196") (pintype "passive"))
    )
    (net (code "146") (name "Net-(rPI1B-VBUS_EN)") (class "Default")
      (node (ref "HB") (pin "12") (pinfunction "12_12") (pintype "passive"))
      (node (ref "rPI1") (pin "111") (pinfunction "VBUS_EN_111") (pintype "passive"))
    )
    (net (code "147") (name "Net-(rxPI1B-CAM0_C_N)") (class "Default")
      (node (ref "H2") (pin "40") (pinfunction "40_40") (pintype "passive"))
      (node (ref "rxPI1") (pin "140") (pinfunction "CAM0_C_N_140") (pintype "passive"))
    )
    (net (code "148") (name "Net-(rxPI1B-CAM0_C_P)") (class "Default")
      (node (ref "H2") (pin "42") (pinfunction "42_42") (pintype "passive"))
      (node (ref "rxPI1") (pin "142") (pinfunction "CAM0_C_P_142") (pintype "passive"))
    )
    (net (code "149") (name "Net-(rxPI1B-CAM0_D0_N)") (class "Default")
      (node (ref "H2") (pin "28") (pinfunction "28_28") (pintype "passive"))
      (node (ref "rxPI1") (pin "128") (pinfunction "CAM0_D0_N_128") (pintype "passive"))
    )
    (net (code "150") (name "Net-(rxPI1B-CAM0_D0_P)") (class "Default")
      (node (ref "H2") (pin "30") (pinfunction "30_30") (pintype "passive"))
      (node (ref "rxPI1") (pin "130") (pinfunction "CAM0_D0_P_130") (pintype "passive"))
    )
    (net (code "151") (name "Net-(rxPI1B-CAM0_D1_N)") (class "Default")
      (node (ref "H2") (pin "34") (pinfunction "34_34") (pintype "passive"))
      (node (ref "rxPI1") (pin "134") (pinfunction "CAM0_D1_N_134") (pintype "passive"))
    )
    (net (code "152") (name "Net-(rxPI1B-CAM0_D1_P)") (class "Default")
      (node (ref "H2") (pin "36") (pinfunction "36_36") (pintype "passive"))
      (node (ref "rxPI1") (pin "136") (pinfunction "CAM0_D1_P_136") (pintype "passive"))
    )
    (net (code "153") (name "Net-(rxPI1B-CAM1_C_N)") (class "Default")
      (node (ref "H2") (pin "27") (pinfunction "27_27") (pintype "passive"))
      (node (ref "rxPI1") (pin "127") (pinfunction "CAM1_C_N_127") (pintype "passive"))
    )
    (net (code "154") (name "Net-(rxPI1B-CAM1_C_P)") (class "Default")
      (node (ref "H2") (pin "29") (pinfunction "29_29") (pintype "passive"))
      (node (ref "rxPI1") (pin "129") (pinfunction "CAM1_C_P_129") (pintype "passive"))
    )
    (net (code "155") (name "Net-(rxPI1B-CAM1_D0_N)") (class "Default")
      (node (ref "H2") (pin "15") (pinfunction "15_15") (pintype "passive"))
      (node (ref "rxPI1") (pin "115") (pinfunction "CAM1_D0_N_115") (pintype "passive"))
    )
    (net (code "156") (name "Net-(rxPI1B-CAM1_D0_P)") (class "Default")
      (node (ref "H2") (pin "17") (pinfunction "17_17") (pintype "passive"))
      (node (ref "rxPI1") (pin "117") (pinfunction "CAM1_D0_P_117") (pintype "passive"))
    )
    (net (code "157") (name "Net-(rxPI1B-CAM1_D1_N)") (class "Default")
      (node (ref "H2") (pin "21") (pinfunction "21_21") (pintype "passive"))
      (node (ref "rxPI1") (pin "121") (pinfunction "CAM1_D1_N_121") (pintype "passive"))
    )
    (net (code "158") (name "Net-(rxPI1B-CAM1_D1_P)") (class "Default")
      (node (ref "H2") (pin "23") (pinfunction "23_23") (pintype "passive"))
      (node (ref "rxPI1") (pin "123") (pinfunction "CAM1_D1_P_123") (pintype "passive"))
    )
    (net (code "159") (name "Net-(rxPI1B-CAM1_D2_N)") (class "Default")
      (node (ref "H2") (pin "33") (pinfunction "33_33") (pintype "passive"))
      (node (ref "rxPI1") (pin "133") (pinfunction "CAM1_D2_N_133") (pintype "passive"))
    )
    (net (code "160") (name "Net-(rxPI1B-CAM1_D2_P)") (class "Default")
      (node (ref "H2") (pin "35") (pinfunction "35_35") (pintype "passive"))
      (node (ref "rxPI1") (pin "135") (pinfunction "CAM1_D2_P_135") (pintype "passive"))
    )
    (net (code "161") (name "Net-(rxPI1B-CAM1_D3_N)") (class "Default")
      (node (ref "H2") (pin "39") (pinfunction "39_39") (pintype "passive"))
      (node (ref "rxPI1") (pin "139") (pinfunction "CAM1_D3_N_139") (pintype "passive"))
    )
    (net (code "162") (name "Net-(rxPI1B-CAM1_D3_P)") (class "Default")
      (node (ref "H2") (pin "41") (pinfunction "41_41") (pintype "passive"))
      (node (ref "rxPI1") (pin "141") (pinfunction "CAM1_D3_P_141") (pintype "passive"))
    )
    (net (code "163") (name "Net-(rxPI1B-DSI0_C_N)") (class "Default")
      (node (ref "H2") (pin "69") (pinfunction "69_69") (pintype "passive"))
      (node (ref "rxPI1") (pin "169") (pinfunction "DSI0_C_N_169") (pintype "passive"))
    )
    (net (code "164") (name "Net-(rxPI1B-DSI0_C_P)") (class "Default")
      (node (ref "H2") (pin "71") (pinfunction "71_71") (pintype "passive"))
      (node (ref "rxPI1") (pin "171") (pinfunction "DSI0_C_P_171") (pintype "passive"))
    )
    (net (code "165") (name "Net-(rxPI1B-DSI0_D0_N)") (class "Default")
      (node (ref "H2") (pin "57") (pinfunction "57_57") (pintype "passive"))
      (node (ref "rxPI1") (pin "157") (pinfunction "DSI0_D0_N_157") (pintype "passive"))
    )
    (net (code "166") (name "Net-(rxPI1B-DSI0_D0_P)") (class "Default")
      (node (ref "H2") (pin "59") (pinfunction "59_59") (pintype "passive"))
      (node (ref "rxPI1") (pin "159") (pinfunction "DSI0_D0_P_159") (pintype "passive"))
    )
    (net (code "167") (name "Net-(rxPI1B-DSI0_D1_N)") (class "Default")
      (node (ref "H2") (pin "63") (pinfunction "63_63") (pintype "passive"))
      (node (ref "rxPI1") (pin "163") (pinfunction "DSI0_D1_N_163") (pintype "passive"))
    )
    (net (code "168") (name "Net-(rxPI1B-DSI0_D1_P)") (class "Default")
      (node (ref "H2") (pin "65") (pinfunction "65_65") (pintype "passive"))
      (node (ref "rxPI1") (pin "165") (pinfunction "DSI0_D1_P_165") (pintype "passive"))
    )
    (net (code "169") (name "Net-(rxPI1B-DSI1_C_N)") (class "Default")
      (node (ref "H2") (pin "87") (pinfunction "87_87") (pintype "passive"))
      (node (ref "rxPI1") (pin "187") (pinfunction "DSI1_C_N_187") (pintype "passive"))
    )
    (net (code "170") (name "Net-(rxPI1B-DSI1_C_P)") (class "Default")
      (node (ref "H2") (pin "89") (pinfunction "89_89") (pintype "passive"))
      (node (ref "rxPI1") (pin "189") (pinfunction "DSI1_C_P_189") (pintype "passive"))
    )
    (net (code "171") (name "Net-(rxPI1B-DSI1_D0_N)") (class "Default")
      (node (ref "H2") (pin "75") (pinfunction "75_75") (pintype "passive"))
      (node (ref "rxPI1") (pin "175") (pinfunction "DSI1_D0_N_175") (pintype "passive"))
    )
    (net (code "172") (name "Net-(rxPI1B-DSI1_D0_P)") (class "Default")
      (node (ref "H2") (pin "77") (pinfunction "77_77") (pintype "passive"))
      (node (ref "rxPI1") (pin "177") (pinfunction "DSI1_D0_P_177") (pintype "passive"))
    )
    (net (code "173") (name "Net-(rxPI1B-DSI1_D1_N)") (class "Default")
      (node (ref "H2") (pin "81") (pinfunction "81_81") (pintype "passive"))
      (node (ref "rxPI1") (pin "181") (pinfunction "DSI1_D1_N_181") (pintype "passive"))
    )
    (net (code "174") (name "Net-(rxPI1B-DSI1_D1_P)") (class "Default")
      (node (ref "H2") (pin "83") (pinfunction "83_83") (pintype "passive"))
      (node (ref "rxPI1") (pin "183") (pinfunction "DSI1_D1_P_183") (pintype "passive"))
    )
    (net (code "175") (name "Net-(rxPI1B-DSI1_D2_N)") (class "Default")
      (node (ref "H2") (pin "93") (pinfunction "93_93") (pintype "passive"))
      (node (ref "rxPI1") (pin "193") (pinfunction "DSI1_D2_N_193") (pintype "passive"))
    )
    (net (code "176") (name "Net-(rxPI1B-DSI1_D2_P)") (class "Default")
      (node (ref "H2") (pin "95") (pinfunction "95_95") (pintype "passive"))
      (node (ref "rxPI1") (pin "195") (pinfunction "DSI1_D2_P_195") (pintype "passive"))
    )
    (net (code "177") (name "Net-(rxPI1B-DSI1_D3_N)") (class "Default")
      (node (ref "H2") (pin "94") (pinfunction "94_94") (pintype "passive"))
      (node (ref "rxPI1") (pin "194") (pinfunction "DSI1_D3_N_194") (pintype "passive"))
    )
    (net (code "178") (name "Net-(rxPI1B-DSI1_D3_P)") (class "Default")
      (node (ref "H2") (pin "96") (pinfunction "96_96") (pintype "passive"))
      (node (ref "rxPI1") (pin "196") (pinfunction "DSI1_D3_P_196") (pintype "passive"))
    )
    (net (code "179") (name "Net-(rxPI1B-USB_OTG_ID)") (class "Default")
      (node (ref "H2") (pin "1") (pinfunction "1_1") (pintype "passive"))
      (node (ref "rxPI1") (pin "101") (pinfunction "USB_OTG_ID_101") (pintype "passive"))
    )
    (net (code "180") (name "Net-(rxPI1B-VDAC_COMP)") (class "Default")
      (node (ref "H2") (pin "11") (pinfunction "11_11") (pintype "passive"))
      (node (ref "rxPI1") (pin "111") (pinfunction "VDAC_COMP_111") (pintype "passive"))
    )
    (net (code "181") (name "Net-(rxPI1C-BT_HOST_WAKE)") (class "Default")
      (node (ref "J3") (pin "86") (pinfunction "86_86") (pintype "passive"))
      (node (ref "rxPI1") (pin "285") (pinfunction "BT_HOST_WAKE_285") (pintype "passive"))
    )
    (net (code "182") (name "Net-(rxPI1C-BT_REG_ON_H)") (class "Default")
      (node (ref "J3") (pin "97") (pinfunction "97_97") (pintype "passive"))
      (node (ref "rxPI1") (pin "298") (pinfunction "BT_REG_ON_H_298") (pintype "passive"))
    )
    (net (code "183") (name "Net-(rxPI1C-GPIO0_C2)") (class "Default")
      (node (ref "J3") (pin "94") (pinfunction "94_94") (pintype "passive"))
      (node (ref "rxPI1") (pin "293") (pinfunction "GPIO0_C2_293") (pintype "passive"))
    )
    (net (code "184") (name "Net-(rxPI1C-GPIO0_D3)") (class "Default")
      (node (ref "J3") (pin "93") (pinfunction "93_93") (pintype "passive"))
      (node (ref "rxPI1") (pin "294") (pinfunction "GPIO0_D3_294") (pintype "passive"))
    )
    (net (code "185") (name "Net-(rxPI1C-GPIO1_B6_CAM2_CLK)") (class "Default")
      (node (ref "J3") (pin "9") (pinfunction "9_9") (pintype "passive"))
      (node (ref "rxPI1") (pin "210") (pinfunction "GPIO1_B6_CAM2_CLK_210") (pintype "passive"))
    )
    (net (code "186") (name "Net-(rxPI1C-GPIO1_B7)") (class "Default")
      (node (ref "J3") (pin "11") (pinfunction "11_11") (pintype "passive"))
      (node (ref "rxPI1") (pin "212") (pinfunction "GPIO1_B7_212") (pintype "passive"))
    )
    (net (code "187") (name "Net-(rxPI1C-GPIO1_C1)") (class "Default")
      (node (ref "J3") (pin "19") (pinfunction "19_19") (pintype "passive"))
      (node (ref "rxPI1") (pin "220") (pinfunction "GPIO1_C1_220") (pintype "passive"))
    )
    (net (code "188") (name "Net-(rxPI1C-GPIO1_C4_S)") (class "Default")
      (node (ref "J3") (pin "80") (pinfunction "80_80") (pintype "passive"))
      (node (ref "rxPI1") (pin "279") (pinfunction "GPIO1_C4_S_279") (pintype "passive"))
    )
    (net (code "189") (name "Net-(rxPI1C-GPIO1_C6_S)") (class "Default")
      (node (ref "J3") (pin "76") (pinfunction "76_76") (pintype "passive"))
      (node (ref "rxPI1") (pin "275") (pinfunction "GPIO1_C6_S_275") (pintype "passive"))
    )
    (net (code "190") (name "Net-(rxPI1C-GPIO1_D0)") (class "Default")
      (node (ref "J3") (pin "43") (pinfunction "43_43") (pintype "passive"))
      (node (ref "rxPI1") (pin "244") (pinfunction "GPIO1_D0_244") (pintype "passive"))
    )
    (net (code "191") (name "Net-(rxPI1C-GPIO1_D1)") (class "Default")
      (node (ref "J3") (pin "45") (pinfunction "45_45") (pintype "passive"))
      (node (ref "rxPI1") (pin "246") (pinfunction "GPIO1_D1_246") (pintype "passive"))
    )
    (net (code "192") (name "Net-(rxPI1C-GPIO1_D2)") (class "Default")
      (node (ref "J3") (pin "84") (pinfunction "84_84") (pintype "passive"))
      (node (ref "rxPI1") (pin "283") (pinfunction "GPIO1_D2_283") (pintype "passive"))
    )
    (net (code "193") (name "Net-(rxPI1C-GPIO1_D5_S)") (class "Default")
      (node (ref "J3") (pin "78") (pinfunction "78_78") (pintype "passive"))
      (node (ref "rxPI1") (pin "277") (pinfunction "GPIO1_D5_S_277") (pintype "passive"))
    )
    (net (code "194") (name "Net-(rxPI1C-GPIO3_B7)") (class "Default")
      (node (ref "J3") (pin "5") (pinfunction "5_5") (pintype "passive"))
      (node (ref "rxPI1") (pin "206") (pinfunction "GPIO3_B7_206") (pintype "passive"))
    )
    (net (code "195") (name "Net-(rxPI1C-GPIO3_C0)") (class "Default")
      (node (ref "J3") (pin "3") (pinfunction "3_3") (pintype "passive"))
      (node (ref "rxPI1") (pin "204") (pinfunction "GPIO3_C0_204") (pintype "passive"))
    )
    (net (code "196") (name "Net-(rxPI1C-GPIO4_A4)") (class "Default")
      (node (ref "J3") (pin "37") (pinfunction "37_37") (pintype "passive"))
      (node (ref "rxPI1") (pin "238") (pinfunction "GPIO4_A4_238") (pintype "passive"))
    )
    (net (code "197") (name "Net-(rxPI1C-GPIO4_A5)") (class "Default")
      (node (ref "J3") (pin "39") (pinfunction "39_39") (pintype "passive"))
      (node (ref "rxPI1") (pin "240") (pinfunction "GPIO4_A5_240") (pintype "passive"))
    )
    (net (code "198") (name "Net-(rxPI1C-GPIO4_A6)") (class "Default")
      (node (ref "J3") (pin "90") (pinfunction "90_90") (pintype "passive"))
      (node (ref "rxPI1") (pin "289") (pinfunction "GPIO4_A6_289") (pintype "passive"))
    )
    (net (code "199") (name "Net-(rxPI1C-GPIO4_A7)") (class "Default")
      (node (ref "J3") (pin "88") (pinfunction "88_88") (pintype "passive"))
      (node (ref "rxPI1") (pin "287") (pinfunction "GPIO4_A7_287") (pintype "passive"))
    )
    (net (code "200") (name "Net-(rxPI1C-HP_DET_L)") (class "Default")
      (node (ref "J3") (pin "35") (pinfunction "35_35") (pintype "passive"))
      (node (ref "rxPI1") (pin "236") (pinfunction "HP_DET_L_236") (pintype "passive"))
    )
    (net (code "201") (name "Net-(rxPI1C-I2C6_SCL_M3)") (class "Default")
      (node (ref "J3") (pin "72") (pinfunction "72_72") (pintype "passive"))
      (node (ref "rxPI1") (pin "271") (pinfunction "I2C6_SCL_M3_271") (pintype "passive"))
    )
    (net (code "202") (name "Net-(rxPI1C-I2C6_SDA_M3)") (class "Default")
      (node (ref "J3") (pin "70") (pinfunction "70_70") (pintype "passive"))
      (node (ref "rxPI1") (pin "269") (pinfunction "I2C6_SDA_M3_269") (pintype "passive"))
    )
    (net (code "203") (name "Net-(rxPI1C-LCD_PWREN_H)") (class "Default")
      (node (ref "J3") (pin "33") (pinfunction "33_33") (pintype "passive"))
      (node (ref "rxPI1") (pin "234") (pinfunction "LCD_PWREN_H_234") (pintype "passive"))
    )
    (net (code "204") (name "Net-(rxPI1C-PCIE20_2_REFCLKN)") (class "Default")
      (node (ref "J3") (pin "42") (pinfunction "42_42") (pintype "passive"))
      (node (ref "rxPI1") (pin "241") (pinfunction "PCIE20_2_REFCLKN_241") (pintype "passive"))
    )
    (net (code "205") (name "Net-(rxPI1C-PCIE20_2_REFCLKP)") (class "Default")
      (node (ref "J3") (pin "40") (pinfunction "40_40") (pintype "passive"))
      (node (ref "rxPI1") (pin "239") (pinfunction "PCIE20_2_REFCLKP_239") (pintype "passive"))
    )
    (net (code "206") (name "Net-(rxPI1C-PWM11_M3)") (class "Default")
      (node (ref "J3") (pin "17") (pinfunction "17_17") (pintype "passive"))
      (node (ref "rxPI1") (pin "218") (pinfunction "PWM11_M3_218") (pintype "passive"))
    )
    (net (code "207") (name "Net-(rxPI1C-RTC_INT_L)") (class "Default")
      (node (ref "J3") (pin "82") (pinfunction "82_82") (pintype "passive"))
      (node (ref "rxPI1") (pin "281") (pinfunction "RTC_INT_L_281") (pintype "passive"))
    )
    (net (code "208") (name "Net-(rxPI1C-SARADC_VIN0_KEY{slash}RECOVERY)") (class "Default")
      (node (ref "J3") (pin "25") (pinfunction "25_25") (pintype "passive"))
      (node (ref "rxPI1") (pin "226") (pinfunction "SARADC_VIN0_KEY/RECOVERY_226") (pintype "passive"))
    )
    (net (code "209") (name "Net-(rxPI1C-SARADC_VIN1_DC)") (class "Default")
      (node (ref "J3") (pin "27") (pinfunction "27_27") (pintype "passive"))
      (node (ref "rxPI1") (pin "228") (pinfunction "SARADC_VIN1_DC_228") (pintype "passive"))
    )
    (net (code "210") (name "Net-(rxPI1C-SARADC_VIN2_HP_HOOK)") (class "Default")
      (node (ref "J3") (pin "29") (pinfunction "29_29") (pintype "passive"))
      (node (ref "rxPI1") (pin "230") (pinfunction "SARADC_VIN2_HP_HOOK_230") (pintype "passive"))
    )
    (net (code "211") (name "Net-(rxPI1C-SDMMC_DET_L)") (class "Default")
      (node (ref "J3") (pin "73") (pinfunction "73_73") (pintype "passive"))
      (node (ref "rxPI1") (pin "274") (pinfunction "SDMMC_DET_L_274") (pintype "passive"))
    )
    (net (code "212") (name "Net-(rxPI1C-TYPEC0_OTG_VBUSDET)") (class "Default")
      (node (ref "J3") (pin "98") (pinfunction "98_98") (pintype "passive"))
      (node (ref "rxPI1") (pin "297") (pinfunction "TYPEC0_OTG_VBUSDET_297") (pintype "passive"))
    )
    (net (code "213") (name "Net-(rxPI1C-TYPEC0_SBU1)") (class "Default")
      (node (ref "J3") (pin "4") (pinfunction "4_4") (pintype "passive"))
      (node (ref "rxPI1") (pin "203") (pinfunction "TYPEC0_SBU1_203") (pintype "passive"))
    )
    (net (code "214") (name "Net-(rxPI1C-TYPEC0_SBU1_DC)") (class "Default")
      (node (ref "J3") (pin "7") (pinfunction "7_7") (pintype "passive"))
      (node (ref "rxPI1") (pin "208") (pinfunction "TYPEC0_SBU1_DC_208") (pintype "passive"))
    )
    (net (code "215") (name "Net-(rxPI1C-TYPEC0_SBU2)") (class "Default")
      (node (ref "J3") (pin "6") (pinfunction "6_6") (pintype "passive"))
      (node (ref "rxPI1") (pin "205") (pinfunction "TYPEC0_SBU2_205") (pintype "passive"))
    )
    (net (code "216") (name "Net-(rxPI1C-TYPEC0_SBU2_DC)") (class "Default")
      (node (ref "J3") (pin "13") (pinfunction "13_13") (pintype "passive"))
      (node (ref "rxPI1") (pin "214") (pinfunction "TYPEC0_SBU2_DC_214") (pintype "passive"))
    )
    (net (code "217") (name "Net-(rxPI1C-TYPEC0_SSRX2N)") (class "Default")
      (node (ref "J3") (pin "24") (pinfunction "24_24") (pintype "passive"))
      (node (ref "rxPI1") (pin "223") (pinfunction "TYPEC0_SSRX2N_223") (pintype "passive"))
    )
    (net (code "218") (name "Net-(rxPI1C-TYPEC0_SSRX2P)") (class "Default")
      (node (ref "J3") (pin "22") (pinfunction "22_22") (pintype "passive"))
      (node (ref "rxPI1") (pin "221") (pinfunction "TYPEC0_SSRX2P_221") (pintype "passive"))
    )
    (net (code "219") (name "Net-(rxPI1C-TYPEC0_SSTX2N)") (class "Default")
      (node (ref "J3") (pin "30") (pinfunction "30_30") (pintype "passive"))
      (node (ref "rxPI1") (pin "229") (pinfunction "TYPEC0_SSTX2N_229") (pintype "passive"))
    )
    (net (code "220") (name "Net-(rxPI1C-TYPEC0_SSTX2P)") (class "Default")
      (node (ref "J3") (pin "28") (pinfunction "28_28") (pintype "passive"))
      (node (ref "rxPI1") (pin "227") (pinfunction "TYPEC0_SSTX2P_227") (pintype "passive"))
    )
    (net (code "221") (name "Net-(rxPI1C-TYPEC5V_PWREN_H)") (class "Default")
      (node (ref "J3") (pin "96") (pinfunction "96_96") (pintype "passive"))
      (node (ref "rxPI1") (pin "295") (pinfunction "TYPEC5V_PWREN_H_295") (pintype "passive"))
    )
    (net (code "222") (name "Net-(rxPI1C-VCC_SD_3V3_S3)") (class "Default")
      (node (ref "J3") (pin "91") (pinfunction "91_91") (pintype "passive"))
      (node (ref "rxPI1") (pin "292") (pinfunction "VCC_SD_3V3_S3_292") (pintype "passive"))
    )
    (net (code "223") (name "Net-(rxPI1C-WIFI_PWR_EN)") (class "Default")
      (node (ref "J3") (pin "23") (pinfunction "23_23") (pintype "passive"))
      (node (ref "rxPI1") (pin "224") (pinfunction "WIFI_PWR_EN_224") (pintype "passive"))
    )
    (net (code "224") (name "PCIe_CLK_N") (class "Default")
      (node (ref "H2") (pin "12") (pinfunction "12_12") (pintype "passive"))
      (node (ref "HB") (pin "11") (pinfunction "11_11") (pintype "passive"))
      (node (ref "rPI1") (pin "112") (pinfunction "PCIe_CLK_N_112") (pintype "passive"))
      (node (ref "rxPI1") (pin "112") (pinfunction "PCIe_CLK_N_112") (pintype "passive"))
    )
    (net (code "225") (name "PCIe_CLK_P") (class "Default")
      (node (ref "H2") (pin "10") (pinfunction "10_10") (pintype "passive"))
      (node (ref "HB") (pin "9") (pinfunction "9_9") (pintype "passive"))
      (node (ref "rPI1") (pin "110") (pinfunction "PCIe_CLK_P_110") (pintype "passive"))
      (node (ref "rxPI1") (pin "110") (pinfunction "PCIe_CLK_P_110") (pintype "passive"))
    )
    (net (code "226") (name "PCIe_CLK_nREQ") (class "Default")
      (node (ref "H2") (pin "2") (pinfunction "2_2") (pintype "passive"))
      (node (ref "HB") (pin "1") (pinfunction "1_1") (pintype "passive"))
      (node (ref "rPI1") (pin "102") (pinfunction "PCIe_CLK_nREQ_102") (pintype "passive"))
      (node (ref "rxPI1") (pin "102") (pinfunction "PCIe_CLK_nREQ_102") (pintype "passive"))
    )
    (net (code "227") (name "PCIe_RX_N") (class "Default")
      (node (ref "H2") (pin "18") (pinfunction "18_18") (pintype "passive"))
      (node (ref "HB") (pin "17") (pinfunction "17_17") (pintype "passive"))
      (node (ref "rPI1") (pin "118") (pinfunction "PCIe_RX_N_118") (pintype "passive"))
      (node (ref "rxPI1") (pin "118") (pinfunction "PCIe_RX_N_118") (pintype "passive"))
    )
    (net (code "228") (name "PCIe_RX_P") (class "Default")
      (node (ref "H2") (pin "16") (pinfunction "16_16") (pintype "passive"))
      (node (ref "HB") (pin "15") (pinfunction "15_15") (pintype "passive"))
      (node (ref "rPI1") (pin "116") (pinfunction "PCIe_RX_P_116") (pintype "passive"))
      (node (ref "rxPI1") (pin "116") (pinfunction "PCIe_RX_P_116") (pintype "passive"))
    )
    (net (code "229") (name "PCIe_TX_N") (class "Default")
      (node (ref "H2") (pin "24") (pinfunction "24_24") (pintype "passive"))
      (node (ref "HB") (pin "23") (pinfunction "23_23") (pintype "passive"))
      (node (ref "rPI1") (pin "124") (pinfunction "PCIe_TX_N_124") (pintype "passive"))
      (node (ref "rxPI1") (pin "124") (pinfunction "PCIe_TX_N_124") (pintype "passive"))
    )
    (net (code "230") (name "PCIe_TX_P") (class "Default")
      (node (ref "H2") (pin "22") (pinfunction "22_22") (pintype "passive"))
      (node (ref "HB") (pin "21") (pinfunction "21_21") (pintype "passive"))
      (node (ref "rPI1") (pin "122") (pinfunction "PCIe_TX_P_122") (pintype "passive"))
      (node (ref "rxPI1") (pin "122") (pinfunction "PCIe_TX_P_122") (pintype "passive"))
    )
    (net (code "231") (name "PCIe_nRST") (class "Default")
      (node (ref "H2") (pin "9") (pinfunction "9_9") (pintype "passive"))
      (node (ref "HB") (pin "10") (pinfunction "10_10") (pintype "passive"))
      (node (ref "rPI1") (pin "109") (pinfunction "PCIe_nRST_109") (pintype "passive"))
      (node (ref "rxPI1") (pin "109") (pinfunction "PCIe_nRST_109") (pintype "passive"))
    )
    (net (code "232") (name "Res104") (class "Default")
      (node (ref "H2") (pin "4") (pinfunction "4_4") (pintype "passive"))
      (node (ref "HB") (pin "3") (pinfunction "3_3") (pintype "passive"))
      (node (ref "rPI1") (pin "104") (pinfunction "PCIE_nWAKE_104") (pintype "passive"))
      (node (ref "rxPI1") (pin "104") (pinfunction "Reserved_104") (pintype "passive"))
    )
    (net (code "233") (name "Res106") (class "Default")
      (node (ref "H2") (pin "6") (pinfunction "6_6") (pintype "passive"))
      (node (ref "HB") (pin "5") (pinfunction "5_5") (pintype "passive"))
      (node (ref "rPI1") (pin "106") (pinfunction "PCIE_PWR_EN_106") (pintype "passive"))
      (node (ref "rxPI1") (pin "106") (pinfunction "Reserved_106") (pintype "passive"))
    )
    (net (code "234") (name "USB2_N") (class "Default")
      (node (ref "J3") (pin "64") (pinfunction "64_64") (pintype "passive"))
      (node (ref "U1") (pin "18") (pinfunction "B0n_18") (pintype "bidirectional"))
      (node (ref "rxPI1") (pin "263") (pinfunction "USB20_HOST0_DP_263") (pintype "passive"))
    )
    (net (code "235") (name "USB2_P") (class "Default")
      (node (ref "J3") (pin "66") (pinfunction "66_66") (pintype "passive"))
      (node (ref "U1") (pin "19") (pinfunction "B0p_19") (pintype "bidirectional"))
      (node (ref "rxPI1") (pin "265") (pinfunction "USB20_HOST0_DM_265") (pintype "passive"))
    )
    (net (code "236") (name "USB30_D_N") (class "Default")
      (node (ref "HB") (pin "35") (pinfunction "35_35") (pintype "passive"))
      (node (ref "U1") (pin "16") (pinfunction "B1n_16") (pintype "bidirectional"))
      (node (ref "rPI1") (pin "136") (pinfunction "USB3-0-D_N_136") (pintype "passive"))
    )
    (net (code "237") (name "USB30_D_P") (class "Default")
      (node (ref "HB") (pin "33") (pinfunction "33_33") (pintype "passive"))
      (node (ref "U1") (pin "17") (pinfunction "B1p_17") (pintype "bidirectional"))
      (node (ref "rPI1") (pin "134") (pinfunction "USB3-0-D_P_134") (pintype "passive"))
    )
    (net (code "238") (name "USB30_RX1_N") (class "Default")
      (node (ref "HB") (pin "27") (pinfunction "27_27") (pintype "passive"))
      (node (ref "J3") (pin "12") (pinfunction "12_12") (pintype "passive"))
      (node (ref "rPI1") (pin "128") (pinfunction "USB3-0-RX_N_128") (pintype "passive"))
      (node (ref "rxPI1") (pin "211") (pinfunction "TYPEC0_SSRX1N_211") (pintype "passive"))
    )
    (net (code "239") (name "USB30_RX1_P") (class "Default")
      (node (ref "HB") (pin "29") (pinfunction "29_29") (pintype "passive"))
      (node (ref "J3") (pin "10") (pinfunction "10_10") (pintype "passive"))
      (node (ref "rPI1") (pin "130") (pinfunction "USB3-0-RX_P_130") (pintype "passive"))
      (node (ref "rxPI1") (pin "209") (pinfunction "TYPEC0_SSRX1P_209") (pintype "passive"))
    )
    (net (code "240") (name "USB30_TX1_N") (class "Default")
      (node (ref "HB") (pin "39") (pinfunction "39_39") (pintype "passive"))
      (node (ref "J3") (pin "18") (pinfunction "18_18") (pintype "passive"))
      (node (ref "rPI1") (pin "140") (pinfunction "USB3-0-TX_N_140") (pintype "passive"))
      (node (ref "rxPI1") (pin "217") (pinfunction "TYPEC0_SSTX1N_217") (pintype "passive"))
    )
    (net (code "241") (name "USB30_TX1_P") (class "Default")
      (node (ref "HB") (pin "41") (pinfunction "41_41") (pintype "passive"))
      (node (ref "J3") (pin "16") (pinfunction "16_16") (pintype "passive"))
      (node (ref "rPI1") (pin "142") (pinfunction "USB3-0-TX_P_142") (pintype "passive"))
      (node (ref "rxPI1") (pin "215") (pinfunction "TYPEC0_SSTX1P_215") (pintype "passive"))
    )
    (net (code "242") (name "USB31_D_N") (class "Default")
      (node (ref "HB") (pin "66") (pinfunction "66_66") (pintype "passive"))
      (node (ref "J3") (pin "48") (pinfunction "48_48") (pintype "passive"))
      (node (ref "rPI1") (pin "165") (pinfunction "USB3-1-D_N_165") (pintype "passive"))
      (node (ref "rxPI1") (pin "247") (pinfunction "USB20_HOST1_DM_247") (pintype "passive"))
    )
    (net (code "243") (name "USB31_D_P") (class "Default")
      (node (ref "HB") (pin "64") (pinfunction "64_64") (pintype "passive"))
      (node (ref "J3") (pin "46") (pinfunction "46_46") (pintype "passive"))
      (node (ref "rPI1") (pin "163") (pinfunction "USB3-1-D_P_163") (pintype "passive"))
      (node (ref "rxPI1") (pin "245") (pinfunction "USB20_HOST1_DP_245") (pintype "passive"))
    )
    (net (code "244") (name "USB31_RX_N") (class "Default")
      (node (ref "HB") (pin "58") (pinfunction "58_58") (pintype "passive"))
      (node (ref "J3") (pin "60") (pinfunction "60_60") (pintype "passive"))
      (node (ref "rPI1") (pin "157") (pinfunction "USB3-1-RX_N_157") (pintype "passive"))
      (node (ref "rxPI1") (pin "259") (pinfunction "C42_-_RXN_259") (pintype "passive"))
    )
    (net (code "245") (name "USB31_RX_P") (class "Default")
      (node (ref "HB") (pin "60") (pinfunction "60_60") (pintype "passive"))
      (node (ref "J3") (pin "58") (pinfunction "58_58") (pintype "passive"))
      (node (ref "rPI1") (pin "159") (pinfunction "USB3-1-RX_P_159") (pintype "passive"))
      (node (ref "rxPI1") (pin "257") (pinfunction "D42_-_RXP_257") (pintype "passive"))
    )
    (net (code "246") (name "USB31_TX_N") (class "Default")
      (node (ref "HB") (pin "70") (pinfunction "70_70") (pintype "passive"))
      (node (ref "J3") (pin "54") (pinfunction "54_54") (pintype "passive"))
      (node (ref "rPI1") (pin "169") (pinfunction "USB3-1-TX_N_169") (pintype "passive"))
      (node (ref "rxPI1") (pin "253") (pinfunction "D41_-_TXN_253") (pintype "passive"))
    )
    (net (code "247") (name "USB31_TX_P") (class "Default")
      (node (ref "HB") (pin "72") (pinfunction "72_72") (pintype "passive"))
      (node (ref "J3") (pin "52") (pinfunction "52_52") (pintype "passive"))
      (node (ref "rPI1") (pin "171") (pinfunction "USB3-1-TX_P_171") (pintype "passive"))
      (node (ref "rxPI1") (pin "251") (pinfunction "E41_-_TXP_251") (pintype "passive"))
    )
    (net (code "248") (name "USBC_D_N") (class "Default")
      (node (ref "H2") (pin "3") (pinfunction "3_3") (pintype "passive"))
      (node (ref "U1") (pin "14") (pinfunction "C0n_14") (pintype "bidirectional"))
      (node (ref "U1") (pin "8") (pinfunction "A1n_8") (pintype "bidirectional"))
      (node (ref "rxPI1") (pin "103") (pinfunction "USB2_N_103") (pintype "passive"))
    )
    (net (code "249") (name "USBC_D_P") (class "Default")
      (node (ref "H2") (pin "5") (pinfunction "5_5") (pintype "passive"))
      (node (ref "U1") (pin "15") (pinfunction "C0p_15") (pintype "bidirectional"))
      (node (ref "U1") (pin "7") (pinfunction "A1p_7") (pintype "bidirectional"))
      (node (ref "rxPI1") (pin "105") (pinfunction "USB2_P_105") (pintype "passive"))
    )
    (net (code "250") (name "USBP_D_N") (class "Default")
      (node (ref "HB") (pin "4") (pinfunction "4_4") (pintype "passive"))
      (node (ref "U1") (pin "4") (pinfunction "A0n_4") (pintype "bidirectional"))
      (node (ref "rPI1") (pin "103") (pinfunction "USB2_N_103") (pintype "passive"))
    )
    (net (code "251") (name "USBP_D_P") (class "Default")
      (node (ref "HB") (pin "6") (pinfunction "6_6") (pintype "passive"))
      (node (ref "U1") (pin "3") (pinfunction "A0p_3") (pintype "bidirectional"))
      (node (ref "rPI1") (pin "105") (pinfunction "USB2_P_105") (pintype "passive"))
    )
    (net (code "252") (name "USB_OTG_ID") (class "Default")
      (node (ref "HB") (pin "2") (pinfunction "2_2") (pintype "passive"))
      (node (ref "R2") (pin "1") (pinfunction "1_1") (pintype "passive"))
      (node (ref "U1") (pin "9") (pinfunction "SEL_9") (pintype "input"))
      (node (ref "rPI1") (pin "101") (pinfunction "USB_OTG_ID_101") (pintype "passive"))
    )
    (net (code "253") (name "VCC_3V3_S3") (class "Default")
      (node (ref "H1") (pin "84") (pinfunction "84_84") (pintype "passive"))
      (node (ref "HA") (pin "83") (pinfunction "83_83") (pintype "passive"))
      (node (ref "U1") (pin "1") (pinfunction "RSVD1_1") (pintype "passive"))
      (node (ref "U1") (pin "10") (pinfunction "RSVD2_10") (pintype "passive"))
      (node (ref "U1") (pin "6") (pinfunction "VCC_6") (pintype "power_in"))
      (node (ref "rPI1") (pin "84") (pinfunction "+3.3v_(Output)_84") (pintype "passive"))
      (node (ref "rxPI1") (pin "84") (pinfunction "+3.3v_(Output)_84") (pintype "passive"))
    )
    (net (code "254") (name "unconnected-(U1-C1n-Pad12)") (class "Default")
      (node (ref "U1") (pin "12") (pinfunction "C1n_12") (pintype "bidirectional"))
    )
    (net (code "255") (name "unconnected-(U1-C1p-Pad13)") (class "Default")
      (node (ref "U1") (pin "13") (pinfunction "C1p_13") (pintype "bidirectional"))
    )
  )
)
